# Power_outputs.net
KiCad netlist of a schematic drawn in Altium Designer
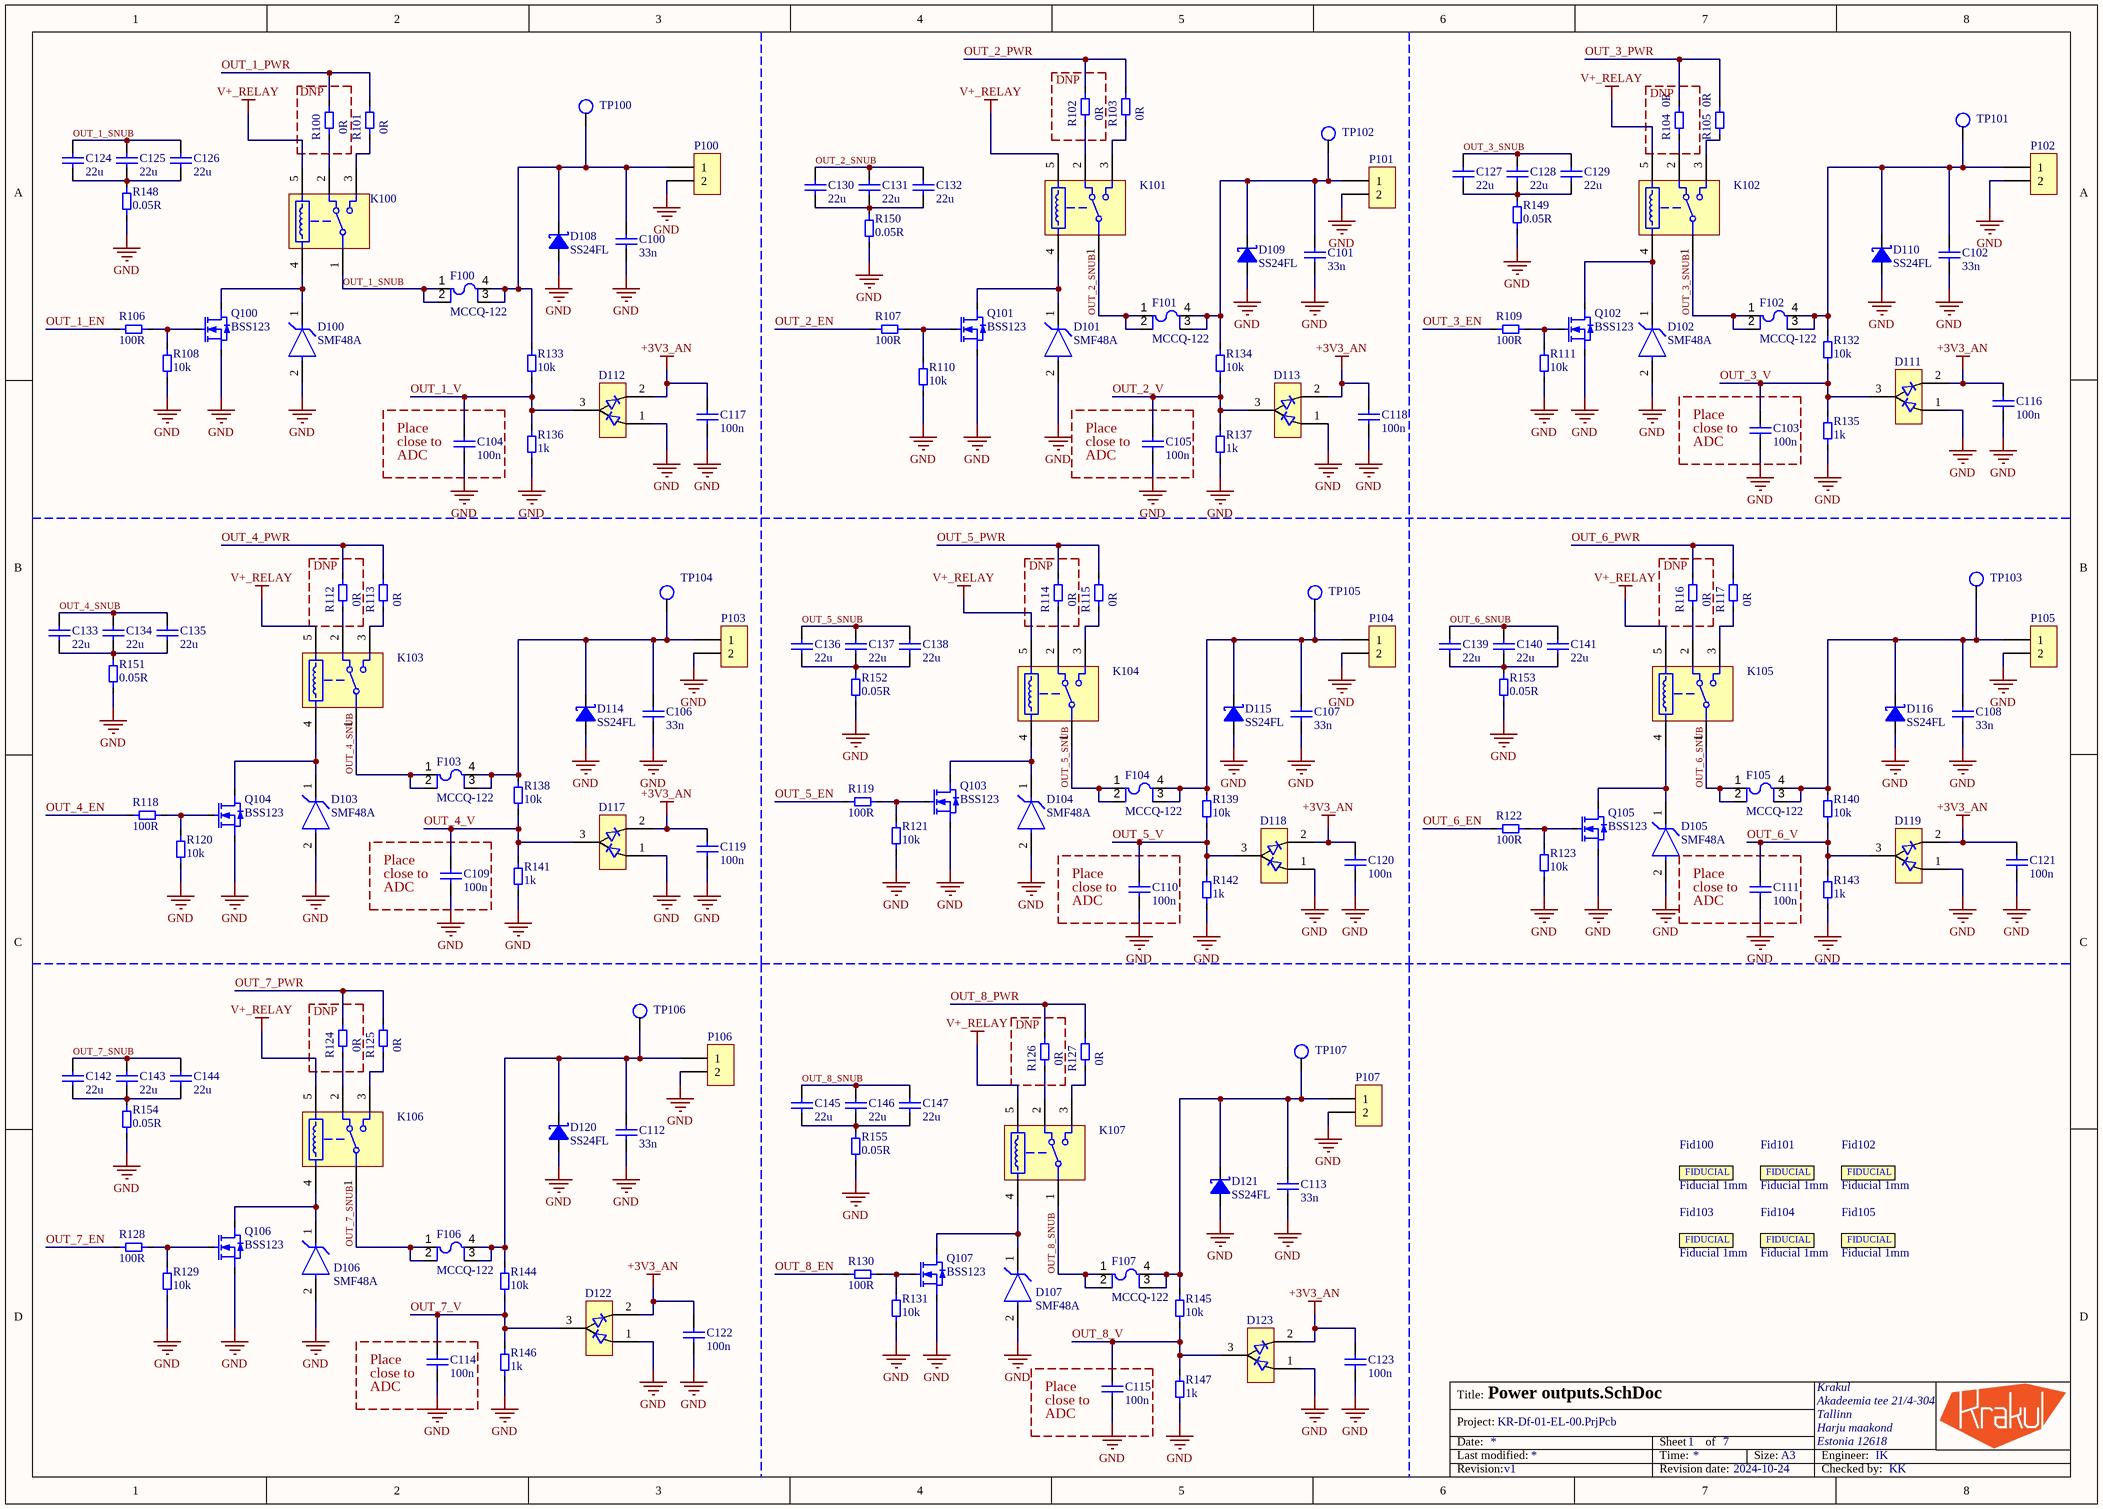
[diagram p0: Power outputs.SchDoc]

(export (version "E")
  (design (tool "Eeschema 10.0.6"))
  (components
    (comp (ref "C100")
      (value "33n")
      (footprint "MLCC_0805_M")
      (description "MLCC, 0805, 33n, 10%, 50V, X7R")
      (fields (field (name "VOLTAGE") "50V") (field (name "TOLERANCE") "10%"))
      (libsource (lib "Krakul Vault") (part "CAPACITOR_NONPOL_IEC"))
    )
    (comp (ref "C101")
      (value "33n")
      (footprint "MLCC_0805_M")
      (description "MLCC, 0805, 33n, 10%, 50V, X7R")
      (fields (field (name "VOLTAGE") "50V") (field (name "TOLERANCE") "10%"))
      (libsource (lib "Krakul Vault") (part "CAPACITOR_NONPOL_IEC"))
    )
    (comp (ref "C102")
      (value "33n")
      (footprint "MLCC_0805_M")
      (description "MLCC, 0805, 33n, 10%, 50V, X7R")
      (fields (field (name "VOLTAGE") "50V") (field (name "TOLERANCE") "10%"))
      (libsource (lib "Krakul Vault") (part "CAPACITOR_NONPOL_IEC"))
    )
    (comp (ref "C103")
      (value "100n")
      (footprint "MLCC_0402_M")
      (description "MLCC, 0402, 100n, 10%, 10V, X5R")
      (fields (field (name "TOLERANCE") "10%") (field (name "MANUFACTURER") "Any"))
      (libsource (lib "Krakul Vault") (part "CAPACITOR_NONPOL_IEC"))
    )
    (comp (ref "C104")
      (value "100n")
      (footprint "MLCC_0402_M")
      (description "MLCC, 0402, 100n, 10%, 10V, X5R")
      (fields (field (name "TOLERANCE") "10%") (field (name "MANUFACTURER") "Any"))
      (libsource (lib "Krakul Vault") (part "CAPACITOR_NONPOL_IEC"))
    )
    (comp (ref "C105")
      (value "100n")
      (footprint "MLCC_0402_M")
      (description "MLCC, 0402, 100n, 10%, 10V, X5R")
      (fields (field (name "TOLERANCE") "10%") (field (name "MANUFACTURER") "Any"))
      (libsource (lib "Krakul Vault") (part "CAPACITOR_NONPOL_IEC"))
    )
    (comp (ref "C106")
      (value "33n")
      (footprint "MLCC_0805_M")
      (description "MLCC, 0805, 33n, 10%, 50V, X7R")
      (fields (field (name "VOLTAGE") "50V") (field (name "TOLERANCE") "10%"))
      (libsource (lib "Krakul Vault") (part "CAPACITOR_NONPOL_IEC"))
    )
    (comp (ref "C107")
      (value "33n")
      (footprint "MLCC_0805_M")
      (description "MLCC, 0805, 33n, 10%, 50V, X7R")
      (fields (field (name "VOLTAGE") "50V") (field (name "TOLERANCE") "10%"))
      (libsource (lib "Krakul Vault") (part "CAPACITOR_NONPOL_IEC"))
    )
    (comp (ref "C108")
      (value "33n")
      (footprint "MLCC_0805_M")
      (description "MLCC, 0805, 33n, 10%, 50V, X7R")
      (fields (field (name "VOLTAGE") "50V") (field (name "TOLERANCE") "10%"))
      (libsource (lib "Krakul Vault") (part "CAPACITOR_NONPOL_IEC"))
    )
    (comp (ref "C109")
      (value "100n")
      (footprint "MLCC_0402_M")
      (description "MLCC, 0402, 100n, 10%, 10V, X5R")
      (fields (field (name "TOLERANCE") "10%") (field (name "MANUFACTURER") "Any"))
      (libsource (lib "Krakul Vault") (part "CAPACITOR_NONPOL_IEC"))
    )
    (comp (ref "C110")
      (value "100n")
      (footprint "MLCC_0402_M")
      (description "MLCC, 0402, 100n, 10%, 10V, X5R")
      (fields (field (name "TOLERANCE") "10%") (field (name "MANUFACTURER") "Any"))
      (libsource (lib "Krakul Vault") (part "CAPACITOR_NONPOL_IEC"))
    )
    (comp (ref "C111")
      (value "100n")
      (footprint "MLCC_0402_M")
      (description "MLCC, 0402, 100n, 10%, 10V, X5R")
      (fields (field (name "TOLERANCE") "10%") (field (name "MANUFACTURER") "Any"))
      (libsource (lib "Krakul Vault") (part "CAPACITOR_NONPOL_IEC"))
    )
    (comp (ref "C112")
      (value "33n")
      (footprint "MLCC_0805_M")
      (description "MLCC, 0805, 33n, 10%, 50V, X7R")
      (fields (field (name "VOLTAGE") "50V") (field (name "TOLERANCE") "10%"))
      (libsource (lib "Krakul Vault") (part "CAPACITOR_NONPOL_IEC"))
    )
    (comp (ref "C113")
      (value "33n")
      (footprint "MLCC_0805_M")
      (description "MLCC, 0805, 33n, 10%, 50V, X7R")
      (fields (field (name "VOLTAGE") "50V") (field (name "TOLERANCE") "10%"))
      (libsource (lib "Krakul Vault") (part "CAPACITOR_NONPOL_IEC"))
    )
    (comp (ref "C114")
      (value "100n")
      (footprint "MLCC_0402_M")
      (description "MLCC, 0402, 100n, 10%, 10V, X5R")
      (fields (field (name "TOLERANCE") "10%") (field (name "MANUFACTURER") "Any"))
      (libsource (lib "Krakul Vault") (part "CAPACITOR_NONPOL_IEC"))
    )
    (comp (ref "C115")
      (value "100n")
      (footprint "MLCC_0402_M")
      (description "MLCC, 0402, 100n, 10%, 10V, X5R")
      (fields (field (name "TOLERANCE") "10%") (field (name "MANUFACTURER") "Any"))
      (libsource (lib "Krakul Vault") (part "CAPACITOR_NONPOL_IEC"))
    )
    (comp (ref "C116")
      (value "100n")
      (footprint "MLCC_0402_M")
      (description "MLCC, 0402, 100n, 10%, 10V, X5R")
      (fields (field (name "TOLERANCE") "10%") (field (name "MANUFACTURER") "Any"))
      (libsource (lib "Krakul Vault") (part "CAPACITOR_NONPOL_IEC"))
    )
    (comp (ref "C117")
      (value "100n")
      (footprint "MLCC_0402_M")
      (description "MLCC, 0402, 100n, 10%, 10V, X5R")
      (fields (field (name "TOLERANCE") "10%") (field (name "MANUFACTURER") "Any"))
      (libsource (lib "Krakul Vault") (part "CAPACITOR_NONPOL_IEC"))
    )
    (comp (ref "C118")
      (value "100n")
      (footprint "MLCC_0402_M")
      (description "MLCC, 0402, 100n, 10%, 10V, X5R")
      (fields (field (name "TOLERANCE") "10%") (field (name "MANUFACTURER") "Any"))
      (libsource (lib "Krakul Vault") (part "CAPACITOR_NONPOL_IEC"))
    )
    (comp (ref "C119")
      (value "100n")
      (footprint "MLCC_0402_M")
      (description "MLCC, 0402, 100n, 10%, 10V, X5R")
      (fields (field (name "TOLERANCE") "10%") (field (name "MANUFACTURER") "Any"))
      (libsource (lib "Krakul Vault") (part "CAPACITOR_NONPOL_IEC"))
    )
    (comp (ref "C120")
      (value "100n")
      (footprint "MLCC_0402_M")
      (description "MLCC, 0402, 100n, 10%, 10V, X5R")
      (fields (field (name "TOLERANCE") "10%") (field (name "MANUFACTURER") "Any"))
      (libsource (lib "Krakul Vault") (part "CAPACITOR_NONPOL_IEC"))
    )
    (comp (ref "C121")
      (value "100n")
      (footprint "MLCC_0402_M")
      (description "MLCC, 0402, 100n, 10%, 10V, X5R")
      (fields (field (name "TOLERANCE") "10%") (field (name "MANUFACTURER") "Any"))
      (libsource (lib "Krakul Vault") (part "CAPACITOR_NONPOL_IEC"))
    )
    (comp (ref "C122")
      (value "100n")
      (footprint "MLCC_0402_M")
      (description "MLCC, 0402, 100n, 10%, 10V, X5R")
      (fields (field (name "TOLERANCE") "10%") (field (name "MANUFACTURER") "Any"))
      (libsource (lib "Krakul Vault") (part "CAPACITOR_NONPOL_IEC"))
    )
    (comp (ref "C123")
      (value "100n")
      (footprint "MLCC_0402_M")
      (description "MLCC, 0402, 100n, 10%, 10V, X5R")
      (fields (field (name "TOLERANCE") "10%") (field (name "MANUFACTURER") "Any"))
      (libsource (lib "Krakul Vault") (part "CAPACITOR_NONPOL_IEC"))
    )
    (comp (ref "C124")
      (value "22u")
      (footprint "MLCC_0805_M")
      (description "MLCC, 0805, 22u, 20%, 35V, X5R")
      (fields (field (name "VOLTAGE") "35V") (field (name "TOLERANCE") "20%"))
      (libsource (lib "Krakul Vault") (part "CAPACITOR_NONPOL_IEC"))
    )
    (comp (ref "C125")
      (value "22u")
      (footprint "MLCC_0805_M")
      (description "MLCC, 0805, 22u, 20%, 35V, X5R")
      (fields (field (name "VOLTAGE") "35V") (field (name "TOLERANCE") "20%"))
      (libsource (lib "Krakul Vault") (part "CAPACITOR_NONPOL_IEC"))
    )
    (comp (ref "C126")
      (value "22u")
      (footprint "MLCC_0805_M")
      (description "MLCC, 0805, 22u, 20%, 35V, X5R")
      (fields (field (name "VOLTAGE") "35V") (field (name "TOLERANCE") "20%"))
      (libsource (lib "Krakul Vault") (part "CAPACITOR_NONPOL_IEC"))
    )
    (comp (ref "C127")
      (value "22u")
      (footprint "MLCC_0805_M")
      (description "MLCC, 0805, 22u, 20%, 35V, X5R")
      (fields (field (name "VOLTAGE") "35V") (field (name "TOLERANCE") "20%"))
      (libsource (lib "Krakul Vault") (part "CAPACITOR_NONPOL_IEC"))
    )
    (comp (ref "C128")
      (value "22u")
      (footprint "MLCC_0805_M")
      (description "MLCC, 0805, 22u, 20%, 35V, X5R")
      (fields (field (name "VOLTAGE") "35V") (field (name "TOLERANCE") "20%"))
      (libsource (lib "Krakul Vault") (part "CAPACITOR_NONPOL_IEC"))
    )
    (comp (ref "C129")
      (value "22u")
      (footprint "MLCC_0805_M")
      (description "MLCC, 0805, 22u, 20%, 35V, X5R")
      (fields (field (name "VOLTAGE") "35V") (field (name "TOLERANCE") "20%"))
      (libsource (lib "Krakul Vault") (part "CAPACITOR_NONPOL_IEC"))
    )
    (comp (ref "C130")
      (value "22u")
      (footprint "MLCC_0805_M")
      (description "MLCC, 0805, 22u, 20%, 35V, X5R")
      (fields (field (name "VOLTAGE") "35V") (field (name "TOLERANCE") "20%"))
      (libsource (lib "Krakul Vault") (part "CAPACITOR_NONPOL_IEC"))
    )
    (comp (ref "C131")
      (value "22u")
      (footprint "MLCC_0805_M")
      (description "MLCC, 0805, 22u, 20%, 35V, X5R")
      (fields (field (name "VOLTAGE") "35V") (field (name "TOLERANCE") "20%"))
      (libsource (lib "Krakul Vault") (part "CAPACITOR_NONPOL_IEC"))
    )
    (comp (ref "C132")
      (value "22u")
      (footprint "MLCC_0805_M")
      (description "MLCC, 0805, 22u, 20%, 35V, X5R")
      (fields (field (name "VOLTAGE") "35V") (field (name "TOLERANCE") "20%"))
      (libsource (lib "Krakul Vault") (part "CAPACITOR_NONPOL_IEC"))
    )
    (comp (ref "C133")
      (value "22u")
      (footprint "MLCC_0805_M")
      (description "MLCC, 0805, 22u, 20%, 35V, X5R")
      (fields (field (name "VOLTAGE") "35V") (field (name "TOLERANCE") "20%"))
      (libsource (lib "Krakul Vault") (part "CAPACITOR_NONPOL_IEC"))
    )
    (comp (ref "C134")
      (value "22u")
      (footprint "MLCC_0805_M")
      (description "MLCC, 0805, 22u, 20%, 35V, X5R")
      (fields (field (name "VOLTAGE") "35V") (field (name "TOLERANCE") "20%"))
      (libsource (lib "Krakul Vault") (part "CAPACITOR_NONPOL_IEC"))
    )
    (comp (ref "C135")
      (value "22u")
      (footprint "MLCC_0805_M")
      (description "MLCC, 0805, 22u, 20%, 35V, X5R")
      (fields (field (name "VOLTAGE") "35V") (field (name "TOLERANCE") "20%"))
      (libsource (lib "Krakul Vault") (part "CAPACITOR_NONPOL_IEC"))
    )
    (comp (ref "C136")
      (value "22u")
      (footprint "MLCC_0805_M")
      (description "MLCC, 0805, 22u, 20%, 35V, X5R")
      (fields (field (name "VOLTAGE") "35V") (field (name "TOLERANCE") "20%"))
      (libsource (lib "Krakul Vault") (part "CAPACITOR_NONPOL_IEC"))
    )
    (comp (ref "C137")
      (value "22u")
      (footprint "MLCC_0805_M")
      (description "MLCC, 0805, 22u, 20%, 35V, X5R")
      (fields (field (name "VOLTAGE") "35V") (field (name "TOLERANCE") "20%"))
      (libsource (lib "Krakul Vault") (part "CAPACITOR_NONPOL_IEC"))
    )
    (comp (ref "C138")
      (value "22u")
      (footprint "MLCC_0805_M")
      (description "MLCC, 0805, 22u, 20%, 35V, X5R")
      (fields (field (name "VOLTAGE") "35V") (field (name "TOLERANCE") "20%"))
      (libsource (lib "Krakul Vault") (part "CAPACITOR_NONPOL_IEC"))
    )
    (comp (ref "C139")
      (value "22u")
      (footprint "MLCC_0805_M")
      (description "MLCC, 0805, 22u, 20%, 35V, X5R")
      (fields (field (name "VOLTAGE") "35V") (field (name "TOLERANCE") "20%"))
      (libsource (lib "Krakul Vault") (part "CAPACITOR_NONPOL_IEC"))
    )
    (comp (ref "C140")
      (value "22u")
      (footprint "MLCC_0805_M")
      (description "MLCC, 0805, 22u, 20%, 35V, X5R")
      (fields (field (name "VOLTAGE") "35V") (field (name "TOLERANCE") "20%"))
      (libsource (lib "Krakul Vault") (part "CAPACITOR_NONPOL_IEC"))
    )
    (comp (ref "C141")
      (value "22u")
      (footprint "MLCC_0805_M")
      (description "MLCC, 0805, 22u, 20%, 35V, X5R")
      (fields (field (name "VOLTAGE") "35V") (field (name "TOLERANCE") "20%"))
      (libsource (lib "Krakul Vault") (part "CAPACITOR_NONPOL_IEC"))
    )
    (comp (ref "C142")
      (value "22u")
      (footprint "MLCC_0805_M")
      (description "MLCC, 0805, 22u, 20%, 35V, X5R")
      (fields (field (name "VOLTAGE") "35V") (field (name "TOLERANCE") "20%"))
      (libsource (lib "Krakul Vault") (part "CAPACITOR_NONPOL_IEC"))
    )
    (comp (ref "C143")
      (value "22u")
      (footprint "MLCC_0805_M")
      (description "MLCC, 0805, 22u, 20%, 35V, X5R")
      (fields (field (name "VOLTAGE") "35V") (field (name "TOLERANCE") "20%"))
      (libsource (lib "Krakul Vault") (part "CAPACITOR_NONPOL_IEC"))
    )
    (comp (ref "C144")
      (value "22u")
      (footprint "MLCC_0805_M")
      (description "MLCC, 0805, 22u, 20%, 35V, X5R")
      (fields (field (name "VOLTAGE") "35V") (field (name "TOLERANCE") "20%"))
      (libsource (lib "Krakul Vault") (part "CAPACITOR_NONPOL_IEC"))
    )
    (comp (ref "C145")
      (value "22u")
      (footprint "MLCC_0805_M")
      (description "MLCC, 0805, 22u, 20%, 35V, X5R")
      (fields (field (name "VOLTAGE") "35V") (field (name "TOLERANCE") "20%"))
      (libsource (lib "Krakul Vault") (part "CAPACITOR_NONPOL_IEC"))
    )
    (comp (ref "C146")
      (value "22u")
      (footprint "MLCC_0805_M")
      (description "MLCC, 0805, 22u, 20%, 35V, X5R")
      (fields (field (name "VOLTAGE") "35V") (field (name "TOLERANCE") "20%"))
      (libsource (lib "Krakul Vault") (part "CAPACITOR_NONPOL_IEC"))
    )
    (comp (ref "C147")
      (value "22u")
      (footprint "MLCC_0805_M")
      (description "MLCC, 0805, 22u, 20%, 35V, X5R")
      (fields (field (name "VOLTAGE") "35V") (field (name "TOLERANCE") "20%"))
      (libsource (lib "Krakul Vault") (part "CAPACITOR_NONPOL_IEC"))
    )
    (comp (ref "D100")
      (value "SMF48A")
      (footprint "FP-SMF48A-MFG")
      (description "Diode TVS Single Uni-Dir 48V 200W 2-Pin SOD-123F T/R")
      (fields (field (name "MANUFACTURER") "Littelfuse"))
      (libsource (lib "Krakul Vault") (part "f813f71cba58e380607f5dd3caf9714"))
    )
    (comp (ref "D101")
      (value "SMF48A")
      (footprint "FP-SMF48A-MFG")
      (description "Diode TVS Single Uni-Dir 48V 200W 2-Pin SOD-123F T/R")
      (fields (field (name "MANUFACTURER") "Littelfuse"))
      (libsource (lib "Krakul Vault") (part "f813f71cba58e380607f5dd3caf9714"))
    )
    (comp (ref "D102")
      (value "SMF48A")
      (footprint "FP-SMF48A-MFG")
      (description "Diode TVS Single Uni-Dir 48V 200W 2-Pin SOD-123F T/R")
      (fields (field (name "MANUFACTURER") "Littelfuse"))
      (libsource (lib "Krakul Vault") (part "f813f71cba58e380607f5dd3caf9714"))
    )
    (comp (ref "D103")
      (value "SMF48A")
      (footprint "FP-SMF48A-MFG")
      (description "Diode TVS Single Uni-Dir 48V 200W 2-Pin SOD-123F T/R")
      (fields (field (name "MANUFACTURER") "Littelfuse"))
      (libsource (lib "Krakul Vault") (part "f813f71cba58e380607f5dd3caf9714"))
    )
    (comp (ref "D104")
      (value "SMF48A")
      (footprint "FP-SMF48A-MFG")
      (description "Diode TVS Single Uni-Dir 48V 200W 2-Pin SOD-123F T/R")
      (fields (field (name "MANUFACTURER") "Littelfuse"))
      (libsource (lib "Krakul Vault") (part "f813f71cba58e380607f5dd3caf9714"))
    )
    (comp (ref "D105")
      (value "SMF48A")
      (footprint "FP-SMF48A-MFG")
      (description "Diode TVS Single Uni-Dir 48V 200W 2-Pin SOD-123F T/R")
      (fields (field (name "MANUFACTURER") "Littelfuse"))
      (libsource (lib "Krakul Vault") (part "f813f71cba58e380607f5dd3caf9714"))
    )
    (comp (ref "D106")
      (value "SMF48A")
      (footprint "FP-SMF48A-MFG")
      (description "Diode TVS Single Uni-Dir 48V 200W 2-Pin SOD-123F T/R")
      (fields (field (name "MANUFACTURER") "Littelfuse"))
      (libsource (lib "Krakul Vault") (part "f813f71cba58e380607f5dd3caf9714"))
    )
    (comp (ref "D107")
      (value "SMF48A")
      (footprint "FP-SMF48A-MFG")
      (description "Diode TVS Single Uni-Dir 48V 200W 2-Pin SOD-123F T/R")
      (fields (field (name "MANUFACTURER") "Littelfuse"))
      (libsource (lib "Krakul Vault") (part "f813f71cba58e380607f5dd3caf9714"))
    )
    (comp (ref "D108")
      (value "SS24FL")
      (footprint "SOD-123F")
      (description "Diode Schottky 40V 2A Surface Mount SOD-123F")
      (fields (field (name "MANUFACTURER") "ON Semiconductor"))
      (libsource (lib "Krakul Vault") (part "Schottky generic 2 pins"))
    )
    (comp (ref "D109")
      (value "SS24FL")
      (footprint "SOD-123F")
      (description "Diode Schottky 40V 2A Surface Mount SOD-123F")
      (fields (field (name "MANUFACTURER") "ON Semiconductor"))
      (libsource (lib "Krakul Vault") (part "Schottky generic 2 pins"))
    )
    (comp (ref "D110")
      (value "SS24FL")
      (footprint "SOD-123F")
      (description "Diode Schottky 40V 2A Surface Mount SOD-123F")
      (fields (field (name "MANUFACTURER") "ON Semiconductor"))
      (libsource (lib "Krakul Vault") (part "Schottky generic 2 pins"))
    )
    (comp (ref "D111")
      (value "BAT6404WH6327XTSA1")
      (footprint "SOT323, SC70")
      (description "Diode Array 1 Pair Series Connection Schottky 40V 120mA Surface Mount SC-70, SOT-323")
      (fields (field (name "MANUFACTURER") "Infineon"))
      (libsource (lib "Krakul Vault") (part "BAT64-04W"))
    )
    (comp (ref "D112")
      (value "BAT6404WH6327XTSA1")
      (footprint "SOT323, SC70")
      (description "Diode Array 1 Pair Series Connection Schottky 40V 120mA Surface Mount SC-70, SOT-323")
      (fields (field (name "MANUFACTURER") "Infineon"))
      (libsource (lib "Krakul Vault") (part "BAT64-04W"))
    )
    (comp (ref "D113")
      (value "BAT6404WH6327XTSA1")
      (footprint "SOT323, SC70")
      (description "Diode Array 1 Pair Series Connection Schottky 40V 120mA Surface Mount SC-70, SOT-323")
      (fields (field (name "MANUFACTURER") "Infineon"))
      (libsource (lib "Krakul Vault") (part "BAT64-04W"))
    )
    (comp (ref "D114")
      (value "SS24FL")
      (footprint "SOD-123F")
      (description "Diode Schottky 40V 2A Surface Mount SOD-123F")
      (fields (field (name "MANUFACTURER") "ON Semiconductor"))
      (libsource (lib "Krakul Vault") (part "Schottky generic 2 pins"))
    )
    (comp (ref "D115")
      (value "SS24FL")
      (footprint "SOD-123F")
      (description "Diode Schottky 40V 2A Surface Mount SOD-123F")
      (fields (field (name "MANUFACTURER") "ON Semiconductor"))
      (libsource (lib "Krakul Vault") (part "Schottky generic 2 pins"))
    )
    (comp (ref "D116")
      (value "SS24FL")
      (footprint "SOD-123F")
      (description "Diode Schottky 40V 2A Surface Mount SOD-123F")
      (fields (field (name "MANUFACTURER") "ON Semiconductor"))
      (libsource (lib "Krakul Vault") (part "Schottky generic 2 pins"))
    )
    (comp (ref "D117")
      (value "BAT6404WH6327XTSA1")
      (footprint "SOT323, SC70")
      (description "Diode Array 1 Pair Series Connection Schottky 40V 120mA Surface Mount SC-70, SOT-323")
      (fields (field (name "MANUFACTURER") "Infineon"))
      (libsource (lib "Krakul Vault") (part "BAT64-04W"))
    )
    (comp (ref "D118")
      (value "BAT6404WH6327XTSA1")
      (footprint "SOT323, SC70")
      (description "Diode Array 1 Pair Series Connection Schottky 40V 120mA Surface Mount SC-70, SOT-323")
      (fields (field (name "MANUFACTURER") "Infineon"))
      (libsource (lib "Krakul Vault") (part "BAT64-04W"))
    )
    (comp (ref "D119")
      (value "BAT6404WH6327XTSA1")
      (footprint "SOT323, SC70")
      (description "Diode Array 1 Pair Series Connection Schottky 40V 120mA Surface Mount SC-70, SOT-323")
      (fields (field (name "MANUFACTURER") "Infineon"))
      (libsource (lib "Krakul Vault") (part "BAT64-04W"))
    )
    (comp (ref "D120")
      (value "SS24FL")
      (footprint "SOD-123F")
      (description "Diode Schottky 40V 2A Surface Mount SOD-123F")
      (fields (field (name "MANUFACTURER") "ON Semiconductor"))
      (libsource (lib "Krakul Vault") (part "Schottky generic 2 pins"))
    )
    (comp (ref "D121")
      (value "SS24FL")
      (footprint "SOD-123F")
      (description "Diode Schottky 40V 2A Surface Mount SOD-123F")
      (fields (field (name "MANUFACTURER") "ON Semiconductor"))
      (libsource (lib "Krakul Vault") (part "Schottky generic 2 pins"))
    )
    (comp (ref "D122")
      (value "BAT6404WH6327XTSA1")
      (footprint "SOT323, SC70")
      (description "Diode Array 1 Pair Series Connection Schottky 40V 120mA Surface Mount SC-70, SOT-323")
      (fields (field (name "MANUFACTURER") "Infineon"))
      (libsource (lib "Krakul Vault") (part "BAT64-04W"))
    )
    (comp (ref "D123")
      (value "BAT6404WH6327XTSA1")
      (footprint "SOT323, SC70")
      (description "Diode Array 1 Pair Series Connection Schottky 40V 120mA Surface Mount SC-70, SOT-323")
      (fields (field (name "MANUFACTURER") "Infineon"))
      (libsource (lib "Krakul Vault") (part "BAT64-04W"))
    )
    (comp (ref "F100")
      (value "MCCQ-122")
      (footprint "MCCQ-122-Footprint-1")
      (description "Fuseholder, Pcb Mount, Mini Blade")
      (fields (field (name "MANUFACTURER") "Multicomp"))
      (libsource (lib "Krakul Vault") (part "MCCQ-122-Symbol-1"))
    )
    (comp (ref "F101")
      (value "MCCQ-122")
      (footprint "MCCQ-122-Footprint-1")
      (description "Fuseholder, Pcb Mount, Mini Blade")
      (fields (field (name "MANUFACTURER") "Multicomp"))
      (libsource (lib "Krakul Vault") (part "MCCQ-122-Symbol-1"))
    )
    (comp (ref "F102")
      (value "MCCQ-122")
      (footprint "MCCQ-122-Footprint-1")
      (description "Fuseholder, Pcb Mount, Mini Blade")
      (fields (field (name "MANUFACTURER") "Multicomp"))
      (libsource (lib "Krakul Vault") (part "MCCQ-122-Symbol-1"))
    )
    (comp (ref "F103")
      (value "MCCQ-122")
      (footprint "MCCQ-122-Footprint-1")
      (description "Fuseholder, Pcb Mount, Mini Blade")
      (fields (field (name "MANUFACTURER") "Multicomp"))
      (libsource (lib "Krakul Vault") (part "MCCQ-122-Symbol-1"))
    )
    (comp (ref "F104")
      (value "MCCQ-122")
      (footprint "MCCQ-122-Footprint-1")
      (description "Fuseholder, Pcb Mount, Mini Blade")
      (fields (field (name "MANUFACTURER") "Multicomp"))
      (libsource (lib "Krakul Vault") (part "MCCQ-122-Symbol-1"))
    )
    (comp (ref "F105")
      (value "MCCQ-122")
      (footprint "MCCQ-122-Footprint-1")
      (description "Fuseholder, Pcb Mount, Mini Blade")
      (fields (field (name "MANUFACTURER") "Multicomp"))
      (libsource (lib "Krakul Vault") (part "MCCQ-122-Symbol-1"))
    )
    (comp (ref "F106")
      (value "MCCQ-122")
      (footprint "MCCQ-122-Footprint-1")
      (description "Fuseholder, Pcb Mount, Mini Blade")
      (fields (field (name "MANUFACTURER") "Multicomp"))
      (libsource (lib "Krakul Vault") (part "MCCQ-122-Symbol-1"))
    )
    (comp (ref "F107")
      (value "MCCQ-122")
      (footprint "MCCQ-122-Footprint-1")
      (description "Fuseholder, Pcb Mount, Mini Blade")
      (fields (field (name "MANUFACTURER") "Multicomp"))
      (libsource (lib "Krakul Vault") (part "MCCQ-122-Symbol-1"))
    )
    (comp (ref "Fid100")
      (value "Fiducial 1mm")
      (footprint "FIDUCIAL 1mm")
      (description "Fiducial, round, 1mm diam")
      (libsource (lib "Krakul Vault") (part "Fiducial"))
    )
    (comp (ref "Fid101")
      (value "Fiducial 1mm")
      (footprint "FIDUCIAL 1mm")
      (description "Fiducial, round, 1mm diam")
      (libsource (lib "Krakul Vault") (part "Fiducial"))
    )
    (comp (ref "Fid102")
      (value "Fiducial 1mm")
      (footprint "FIDUCIAL 1mm")
      (description "Fiducial, round, 1mm diam")
      (libsource (lib "Krakul Vault") (part "Fiducial"))
    )
    (comp (ref "Fid103")
      (value "Fiducial 1mm")
      (footprint "FIDUCIAL 1mm")
      (description "Fiducial, round, 1mm diam")
      (libsource (lib "Krakul Vault") (part "Fiducial"))
    )
    (comp (ref "Fid104")
      (value "Fiducial 1mm")
      (footprint "FIDUCIAL 1mm")
      (description "Fiducial, round, 1mm diam")
      (libsource (lib "Krakul Vault") (part "Fiducial"))
    )
    (comp (ref "Fid105")
      (value "Fiducial 1mm")
      (footprint "FIDUCIAL 1mm")
      (description "Fiducial, round, 1mm diam")
      (libsource (lib "Krakul Vault") (part "Fiducial"))
    )
    (comp (ref "K100")
      (value "J107F1CS205VDC.45")
      (footprint "J107F1CS205VDC.45")
      (description "RELAY GEN PURPOSE SPDT 20A 5V")
      (fields (field (name "MANUFACTURER") "CIT Relay and Switch"))
      (libsource (lib "Krakul Vault") (part "J107F1CS205VDC.45"))
    )
    (comp (ref "K101")
      (value "J107F1CS205VDC.45")
      (footprint "J107F1CS205VDC.45")
      (description "RELAY GEN PURPOSE SPDT 20A 5V")
      (fields (field (name "MANUFACTURER") "CIT Relay and Switch"))
      (libsource (lib "Krakul Vault") (part "J107F1CS205VDC.45"))
    )
    (comp (ref "K102")
      (value "J107F1CS205VDC.45")
      (footprint "J107F1CS205VDC.45")
      (description "RELAY GEN PURPOSE SPDT 20A 5V")
      (fields (field (name "MANUFACTURER") "CIT Relay and Switch"))
      (libsource (lib "Krakul Vault") (part "J107F1CS205VDC.45"))
    )
    (comp (ref "K103")
      (value "J107F1CS205VDC.45")
      (footprint "J107F1CS205VDC.45")
      (description "RELAY GEN PURPOSE SPDT 20A 5V")
      (fields (field (name "MANUFACTURER") "CIT Relay and Switch"))
      (libsource (lib "Krakul Vault") (part "J107F1CS205VDC.45"))
    )
    (comp (ref "K104")
      (value "J107F1CS205VDC.45")
      (footprint "J107F1CS205VDC.45")
      (description "RELAY GEN PURPOSE SPDT 20A 5V")
      (fields (field (name "MANUFACTURER") "CIT Relay and Switch"))
      (libsource (lib "Krakul Vault") (part "J107F1CS205VDC.45"))
    )
    (comp (ref "K105")
      (value "J107F1CS205VDC.45")
      (footprint "J107F1CS205VDC.45")
      (description "RELAY GEN PURPOSE SPDT 20A 5V")
      (fields (field (name "MANUFACTURER") "CIT Relay and Switch"))
      (libsource (lib "Krakul Vault") (part "J107F1CS205VDC.45"))
    )
    (comp (ref "K106")
      (value "J107F1CS205VDC.45")
      (footprint "J107F1CS205VDC.45")
      (description "RELAY GEN PURPOSE SPDT 20A 5V")
      (fields (field (name "MANUFACTURER") "CIT Relay and Switch"))
      (libsource (lib "Krakul Vault") (part "J107F1CS205VDC.45"))
    )
    (comp (ref "K107")
      (value "J107F1CS205VDC.45")
      (footprint "J107F1CS205VDC.45")
      (description "RELAY GEN PURPOSE SPDT 20A 5V")
      (fields (field (name "MANUFACTURER") "CIT Relay and Switch"))
      (libsource (lib "Krakul Vault") (part "J107F1CS205VDC.45"))
    )
    (comp (ref "P100")
      (value "DGPS2.5R-5.0-02P")
      (footprint "DGPS2.5R-5.0-02P-Footprint-1")
      (description "Spring loaded terminal block")
      (fields (field (name "MANUFACTURER") "Degson"))
      (libsource (lib "Krakul Vault") (part "2POS GENERIC"))
    )
    (comp (ref "P101")
      (value "DGPS2.5R-5.0-02P")
      (footprint "DGPS2.5R-5.0-02P-Footprint-1")
      (description "Spring loaded terminal block")
      (fields (field (name "MANUFACTURER") "Degson"))
      (libsource (lib "Krakul Vault") (part "2POS GENERIC"))
    )
    (comp (ref "P102")
      (value "DGPS2.5R-5.0-02P")
      (footprint "DGPS2.5R-5.0-02P-Footprint-1")
      (description "Spring loaded terminal block")
      (fields (field (name "MANUFACTURER") "Degson"))
      (libsource (lib "Krakul Vault") (part "2POS GENERIC"))
    )
    (comp (ref "P103")
      (value "DGPS2.5R-5.0-02P")
      (footprint "DGPS2.5R-5.0-02P-Footprint-1")
      (description "Spring loaded terminal block")
      (fields (field (name "MANUFACTURER") "Degson"))
      (libsource (lib "Krakul Vault") (part "2POS GENERIC"))
    )
    (comp (ref "P104")
      (value "DGPS2.5R-5.0-02P")
      (footprint "DGPS2.5R-5.0-02P-Footprint-1")
      (description "Spring loaded terminal block")
      (fields (field (name "MANUFACTURER") "Degson"))
      (libsource (lib "Krakul Vault") (part "2POS GENERIC"))
    )
    (comp (ref "P105")
      (value "DGPS2.5R-5.0-02P")
      (footprint "DGPS2.5R-5.0-02P-Footprint-1")
      (description "Spring loaded terminal block")
      (fields (field (name "MANUFACTURER") "Degson"))
      (libsource (lib "Krakul Vault") (part "2POS GENERIC"))
    )
    (comp (ref "P106")
      (value "DGPS2.5R-5.0-02P")
      (footprint "DGPS2.5R-5.0-02P-Footprint-1")
      (description "Spring loaded terminal block")
      (fields (field (name "MANUFACTURER") "Degson"))
      (libsource (lib "Krakul Vault") (part "2POS GENERIC"))
    )
    (comp (ref "P107")
      (value "DGPS2.5R-5.0-02P")
      (footprint "DGPS2.5R-5.0-02P-Footprint-1")
      (description "Spring loaded terminal block")
      (fields (field (name "MANUFACTURER") "Degson"))
      (libsource (lib "Krakul Vault") (part "2POS GENERIC"))
    )
    (comp (ref "Q100")
      (value "BSS123")
      (footprint "SOT-23-3")
      (description "MOSFET N-CH 100V 170MA SOT-23")
      (fields (field (name "MANUFACTURER") "ON Semiconductor") (field (name "VOLTAGE") "100V"))
      (libsource (lib "Krakul Vault") (part "N-CH MOSFET 3-pin SOT"))
    )
    (comp (ref "Q101")
      (value "BSS123")
      (footprint "SOT-23-3")
      (description "MOSFET N-CH 100V 170MA SOT-23")
      (fields (field (name "MANUFACTURER") "ON Semiconductor") (field (name "VOLTAGE") "100V"))
      (libsource (lib "Krakul Vault") (part "N-CH MOSFET 3-pin SOT"))
    )
    (comp (ref "Q102")
      (value "BSS123")
      (footprint "SOT-23-3")
      (description "MOSFET N-CH 100V 170MA SOT-23")
      (fields (field (name "MANUFACTURER") "ON Semiconductor") (field (name "VOLTAGE") "100V"))
      (libsource (lib "Krakul Vault") (part "N-CH MOSFET 3-pin SOT"))
    )
    (comp (ref "Q103")
      (value "BSS123")
      (footprint "SOT-23-3")
      (description "MOSFET N-CH 100V 170MA SOT-23")
      (fields (field (name "MANUFACTURER") "ON Semiconductor") (field (name "VOLTAGE") "100V"))
      (libsource (lib "Krakul Vault") (part "N-CH MOSFET 3-pin SOT"))
    )
    (comp (ref "Q104")
      (value "BSS123")
      (footprint "SOT-23-3")
      (description "MOSFET N-CH 100V 170MA SOT-23")
      (fields (field (name "MANUFACTURER") "ON Semiconductor") (field (name "VOLTAGE") "100V"))
      (libsource (lib "Krakul Vault") (part "N-CH MOSFET 3-pin SOT"))
    )
    (comp (ref "Q105")
      (value "BSS123")
      (footprint "SOT-23-3")
      (description "MOSFET N-CH 100V 170MA SOT-23")
      (fields (field (name "MANUFACTURER") "ON Semiconductor") (field (name "VOLTAGE") "100V"))
      (libsource (lib "Krakul Vault") (part "N-CH MOSFET 3-pin SOT"))
    )
    (comp (ref "Q106")
      (value "BSS123")
      (footprint "SOT-23-3")
      (description "MOSFET N-CH 100V 170MA SOT-23")
      (fields (field (name "MANUFACTURER") "ON Semiconductor") (field (name "VOLTAGE") "100V"))
      (libsource (lib "Krakul Vault") (part "N-CH MOSFET 3-pin SOT"))
    )
    (comp (ref "Q107")
      (value "BSS123")
      (footprint "SOT-23-3")
      (description "MOSFET N-CH 100V 170MA SOT-23")
      (fields (field (name "MANUFACTURER") "ON Semiconductor") (field (name "VOLTAGE") "100V"))
      (libsource (lib "Krakul Vault") (part "N-CH MOSFET 3-pin SOT"))
    )
    (comp (ref "R100")
      (value "TLRZ2BTTD")
      (footprint "TLRZ2BTTD-Footprint-1")
      (description "Res Metal Plate 1206 0 Ohm Sulfur Resistant Pad SMD Automotive T/R")
      (fields (field (name "MANUFACTURER") "KOA Speer Electronics") (field (name "VALUE 2") "0R"))
      (libsource (lib "Krakul Vault") (part "RESISTOR_GENERIC_IEC"))
    )
    (comp (ref "R101")
      (value "TLRZ2BTTD")
      (footprint "TLRZ2BTTD-Footprint-1")
      (description "Res Metal Plate 1206 0 Ohm Sulfur Resistant Pad SMD Automotive T/R")
      (fields (field (name "MANUFACTURER") "KOA Speer Electronics") (field (name "VALUE 2") "0R"))
      (libsource (lib "Krakul Vault") (part "RESISTOR_GENERIC_IEC"))
    )
    (comp (ref "R102")
      (value "TLRZ2BTTD")
      (footprint "TLRZ2BTTD-Footprint-1")
      (description "Res Metal Plate 1206 0 Ohm Sulfur Resistant Pad SMD Automotive T/R")
      (fields (field (name "MANUFACTURER") "KOA Speer Electronics") (field (name "VALUE 2") "0R"))
      (libsource (lib "Krakul Vault") (part "RESISTOR_GENERIC_IEC"))
    )
    (comp (ref "R103")
      (value "TLRZ2BTTD")
      (footprint "TLRZ2BTTD-Footprint-1")
      (description "Res Metal Plate 1206 0 Ohm Sulfur Resistant Pad SMD Automotive T/R")
      (fields (field (name "MANUFACTURER") "KOA Speer Electronics") (field (name "VALUE 2") "0R"))
      (libsource (lib "Krakul Vault") (part "RESISTOR_GENERIC_IEC"))
    )
    (comp (ref "R104")
      (value "TLRZ2BTTD")
      (footprint "TLRZ2BTTD-Footprint-1")
      (description "Res Metal Plate 1206 0 Ohm Sulfur Resistant Pad SMD Automotive T/R")
      (fields (field (name "MANUFACTURER") "KOA Speer Electronics") (field (name "VALUE 2") "0R"))
      (libsource (lib "Krakul Vault") (part "RESISTOR_GENERIC_IEC"))
    )
    (comp (ref "R105")
      (value "TLRZ2BTTD")
      (footprint "TLRZ2BTTD-Footprint-1")
      (description "Res Metal Plate 1206 0 Ohm Sulfur Resistant Pad SMD Automotive T/R")
      (fields (field (name "MANUFACTURER") "KOA Speer Electronics") (field (name "VALUE 2") "0R"))
      (libsource (lib "Krakul Vault") (part "RESISTOR_GENERIC_IEC"))
    )
    (comp (ref "R106")
      (value "100R")
      (footprint "Resistor_0603_M")
      (description "Resistor, 0603, 100R, 1%, 1/10W")
      (fields (field (name "TOLERANCE") "1%") (field (name "POWER") "100mW"))
      (libsource (lib "Krakul Vault") (part "RESISTOR_GENERIC_IEC"))
    )
    (comp (ref "R107")
      (value "100R")
      (footprint "Resistor_0603_M")
      (description "Resistor, 0603, 100R, 1%, 1/10W")
      (fields (field (name "TOLERANCE") "1%") (field (name "POWER") "100mW"))
      (libsource (lib "Krakul Vault") (part "RESISTOR_GENERIC_IEC"))
    )
    (comp (ref "R108")
      (value "10k")
      (footprint "Resistor_0603_M")
      (description "Resistor, 0603, 10k, 1%, 1/10W")
      (fields (field (name "MANUFACTURER") "Any") (field (name "TOLERANCE") "1%"))
      (libsource (lib "Krakul Vault") (part "RESISTOR_GENERIC_IEC"))
    )
    (comp (ref "R109")
      (value "100R")
      (footprint "Resistor_0603_M")
      (description "Resistor, 0603, 100R, 1%, 1/10W")
      (fields (field (name "TOLERANCE") "1%") (field (name "POWER") "100mW"))
      (libsource (lib "Krakul Vault") (part "RESISTOR_GENERIC_IEC"))
    )
    (comp (ref "R110")
      (value "10k")
      (footprint "Resistor_0603_M")
      (description "Resistor, 0603, 10k, 1%, 1/10W")
      (fields (field (name "MANUFACTURER") "Any") (field (name "TOLERANCE") "1%"))
      (libsource (lib "Krakul Vault") (part "RESISTOR_GENERIC_IEC"))
    )
    (comp (ref "R111")
      (value "10k")
      (footprint "Resistor_0603_M")
      (description "Resistor, 0603, 10k, 1%, 1/10W")
      (fields (field (name "MANUFACTURER") "Any") (field (name "TOLERANCE") "1%"))
      (libsource (lib "Krakul Vault") (part "RESISTOR_GENERIC_IEC"))
    )
    (comp (ref "R112")
      (value "TLRZ2BTTD")
      (footprint "TLRZ2BTTD-Footprint-1")
      (description "Res Metal Plate 1206 0 Ohm Sulfur Resistant Pad SMD Automotive T/R")
      (fields (field (name "MANUFACTURER") "KOA Speer Electronics") (field (name "VALUE 2") "0R"))
      (libsource (lib "Krakul Vault") (part "RESISTOR_GENERIC_IEC"))
    )
    (comp (ref "R113")
      (value "TLRZ2BTTD")
      (footprint "TLRZ2BTTD-Footprint-1")
      (description "Res Metal Plate 1206 0 Ohm Sulfur Resistant Pad SMD Automotive T/R")
      (fields (field (name "MANUFACTURER") "KOA Speer Electronics") (field (name "VALUE 2") "0R"))
      (libsource (lib "Krakul Vault") (part "RESISTOR_GENERIC_IEC"))
    )
    (comp (ref "R114")
      (value "TLRZ2BTTD")
      (footprint "TLRZ2BTTD-Footprint-1")
      (description "Res Metal Plate 1206 0 Ohm Sulfur Resistant Pad SMD Automotive T/R")
      (fields (field (name "MANUFACTURER") "KOA Speer Electronics") (field (name "VALUE 2") "0R"))
      (libsource (lib "Krakul Vault") (part "RESISTOR_GENERIC_IEC"))
    )
    (comp (ref "R115")
      (value "TLRZ2BTTD")
      (footprint "TLRZ2BTTD-Footprint-1")
      (description "Res Metal Plate 1206 0 Ohm Sulfur Resistant Pad SMD Automotive T/R")
      (fields (field (name "MANUFACTURER") "KOA Speer Electronics") (field (name "VALUE 2") "0R"))
      (libsource (lib "Krakul Vault") (part "RESISTOR_GENERIC_IEC"))
    )
    (comp (ref "R116")
      (value "TLRZ2BTTD")
      (footprint "TLRZ2BTTD-Footprint-1")
      (description "Res Metal Plate 1206 0 Ohm Sulfur Resistant Pad SMD Automotive T/R")
      (fields (field (name "MANUFACTURER") "KOA Speer Electronics") (field (name "VALUE 2") "0R"))
      (libsource (lib "Krakul Vault") (part "RESISTOR_GENERIC_IEC"))
    )
    (comp (ref "R117")
      (value "TLRZ2BTTD")
      (footprint "TLRZ2BTTD-Footprint-1")
      (description "Res Metal Plate 1206 0 Ohm Sulfur Resistant Pad SMD Automotive T/R")
      (fields (field (name "MANUFACTURER") "KOA Speer Electronics") (field (name "VALUE 2") "0R"))
      (libsource (lib "Krakul Vault") (part "RESISTOR_GENERIC_IEC"))
    )
    (comp (ref "R118")
      (value "100R")
      (footprint "Resistor_0603_M")
      (description "Resistor, 0603, 100R, 1%, 1/10W")
      (fields (field (name "TOLERANCE") "1%") (field (name "POWER") "100mW"))
      (libsource (lib "Krakul Vault") (part "RESISTOR_GENERIC_IEC"))
    )
    (comp (ref "R119")
      (value "100R")
      (footprint "Resistor_0603_M")
      (description "Resistor, 0603, 100R, 1%, 1/10W")
      (fields (field (name "TOLERANCE") "1%") (field (name "POWER") "100mW"))
      (libsource (lib "Krakul Vault") (part "RESISTOR_GENERIC_IEC"))
    )
    (comp (ref "R120")
      (value "10k")
      (footprint "Resistor_0603_M")
      (description "Resistor, 0603, 10k, 1%, 1/10W")
      (fields (field (name "MANUFACTURER") "Any") (field (name "TOLERANCE") "1%"))
      (libsource (lib "Krakul Vault") (part "RESISTOR_GENERIC_IEC"))
    )
    (comp (ref "R121")
      (value "10k")
      (footprint "Resistor_0603_M")
      (description "Resistor, 0603, 10k, 1%, 1/10W")
      (fields (field (name "MANUFACTURER") "Any") (field (name "TOLERANCE") "1%"))
      (libsource (lib "Krakul Vault") (part "RESISTOR_GENERIC_IEC"))
    )
    (comp (ref "R122")
      (value "100R")
      (footprint "Resistor_0603_M")
      (description "Resistor, 0603, 100R, 1%, 1/10W")
      (fields (field (name "TOLERANCE") "1%") (field (name "POWER") "100mW"))
      (libsource (lib "Krakul Vault") (part "RESISTOR_GENERIC_IEC"))
    )
    (comp (ref "R123")
      (value "10k")
      (footprint "Resistor_0603_M")
      (description "Resistor, 0603, 10k, 1%, 1/10W")
      (fields (field (name "MANUFACTURER") "Any") (field (name "TOLERANCE") "1%"))
      (libsource (lib "Krakul Vault") (part "RESISTOR_GENERIC_IEC"))
    )
    (comp (ref "R124")
      (value "TLRZ2BTTD")
      (footprint "TLRZ2BTTD-Footprint-1")
      (description "Res Metal Plate 1206 0 Ohm Sulfur Resistant Pad SMD Automotive T/R")
      (fields (field (name "MANUFACTURER") "KOA Speer Electronics") (field (name "VALUE 2") "0R"))
      (libsource (lib "Krakul Vault") (part "RESISTOR_GENERIC_IEC"))
    )
    (comp (ref "R125")
      (value "TLRZ2BTTD")
      (footprint "TLRZ2BTTD-Footprint-1")
      (description "Res Metal Plate 1206 0 Ohm Sulfur Resistant Pad SMD Automotive T/R")
      (fields (field (name "MANUFACTURER") "KOA Speer Electronics") (field (name "VALUE 2") "0R"))
      (libsource (lib "Krakul Vault") (part "RESISTOR_GENERIC_IEC"))
    )
    (comp (ref "R126")
      (value "TLRZ2BTTD")
      (footprint "TLRZ2BTTD-Footprint-1")
      (description "Res Metal Plate 1206 0 Ohm Sulfur Resistant Pad SMD Automotive T/R")
      (fields (field (name "MANUFACTURER") "KOA Speer Electronics") (field (name "VALUE 2") "0R"))
      (libsource (lib "Krakul Vault") (part "RESISTOR_GENERIC_IEC"))
    )
    (comp (ref "R127")
      (value "TLRZ2BTTD")
      (footprint "TLRZ2BTTD-Footprint-1")
      (description "Res Metal Plate 1206 0 Ohm Sulfur Resistant Pad SMD Automotive T/R")
      (fields (field (name "MANUFACTURER") "KOA Speer Electronics") (field (name "VALUE 2") "0R"))
      (libsource (lib "Krakul Vault") (part "RESISTOR_GENERIC_IEC"))
    )
    (comp (ref "R128")
      (value "100R")
      (footprint "Resistor_0603_M")
      (description "Resistor, 0603, 100R, 1%, 1/10W")
      (fields (field (name "TOLERANCE") "1%") (field (name "POWER") "100mW"))
      (libsource (lib "Krakul Vault") (part "RESISTOR_GENERIC_IEC"))
    )
    (comp (ref "R129")
      (value "10k")
      (footprint "Resistor_0603_M")
      (description "Resistor, 0603, 10k, 1%, 1/10W")
      (fields (field (name "MANUFACTURER") "Any") (field (name "TOLERANCE") "1%"))
      (libsource (lib "Krakul Vault") (part "RESISTOR_GENERIC_IEC"))
    )
    (comp (ref "R130")
      (value "100R")
      (footprint "Resistor_0603_M")
      (description "Resistor, 0603, 100R, 1%, 1/10W")
      (fields (field (name "TOLERANCE") "1%") (field (name "POWER") "100mW"))
      (libsource (lib "Krakul Vault") (part "RESISTOR_GENERIC_IEC"))
    )
    (comp (ref "R131")
      (value "10k")
      (footprint "Resistor_0603_M")
      (description "Resistor, 0603, 10k, 1%, 1/10W")
      (fields (field (name "MANUFACTURER") "Any") (field (name "TOLERANCE") "1%"))
      (libsource (lib "Krakul Vault") (part "RESISTOR_GENERIC_IEC"))
    )
    (comp (ref "R132")
      (value "10k")
      (footprint "Resistor_0603_M")
      (description "Resistor, 0603, 10k, 1%, 1/10W")
      (fields (field (name "MANUFACTURER") "Any") (field (name "TOLERANCE") "1%"))
      (libsource (lib "Krakul Vault") (part "RESISTOR_GENERIC_IEC"))
    )
    (comp (ref "R133")
      (value "10k")
      (footprint "Resistor_0603_M")
      (description "Resistor, 0603, 10k, 1%, 1/10W")
      (fields (field (name "MANUFACTURER") "Any") (field (name "TOLERANCE") "1%"))
      (libsource (lib "Krakul Vault") (part "RESISTOR_GENERIC_IEC"))
    )
    (comp (ref "R134")
      (value "10k")
      (footprint "Resistor_0603_M")
      (description "Resistor, 0603, 10k, 1%, 1/10W")
      (fields (field (name "MANUFACTURER") "Any") (field (name "TOLERANCE") "1%"))
      (libsource (lib "Krakul Vault") (part "RESISTOR_GENERIC_IEC"))
    )
    (comp (ref "R135")
      (value "1k")
      (footprint "Resistor_0603_M")
      (description "Resistor, 0603, 1k, 0.1%, 1/16W")
      (fields (field (name "MANUFACTURER") "Any"))
      (libsource (lib "Krakul Vault") (part "RESISTOR_GENERIC_IEC"))
    )
    (comp (ref "R136")
      (value "1k")
      (footprint "Resistor_0603_M")
      (description "Resistor, 0603, 1k, 0.1%, 1/16W")
      (fields (field (name "MANUFACTURER") "Any"))
      (libsource (lib "Krakul Vault") (part "RESISTOR_GENERIC_IEC"))
    )
    (comp (ref "R137")
      (value "1k")
      (footprint "Resistor_0603_M")
      (description "Resistor, 0603, 1k, 0.1%, 1/16W")
      (fields (field (name "MANUFACTURER") "Any"))
      (libsource (lib "Krakul Vault") (part "RESISTOR_GENERIC_IEC"))
    )
    (comp (ref "R138")
      (value "10k")
      (footprint "Resistor_0603_M")
      (description "Resistor, 0603, 10k, 1%, 1/10W")
      (fields (field (name "MANUFACTURER") "Any") (field (name "TOLERANCE") "1%"))
      (libsource (lib "Krakul Vault") (part "RESISTOR_GENERIC_IEC"))
    )
    (comp (ref "R139")
      (value "10k")
      (footprint "Resistor_0603_M")
      (description "Resistor, 0603, 10k, 1%, 1/10W")
      (fields (field (name "MANUFACTURER") "Any") (field (name "TOLERANCE") "1%"))
      (libsource (lib "Krakul Vault") (part "RESISTOR_GENERIC_IEC"))
    )
    (comp (ref "R140")
      (value "10k")
      (footprint "Resistor_0603_M")
      (description "Resistor, 0603, 10k, 1%, 1/10W")
      (fields (field (name "MANUFACTURER") "Any") (field (name "TOLERANCE") "1%"))
      (libsource (lib "Krakul Vault") (part "RESISTOR_GENERIC_IEC"))
    )
    (comp (ref "R141")
      (value "1k")
      (footprint "Resistor_0603_M")
      (description "Resistor, 0603, 1k, 0.1%, 1/16W")
      (fields (field (name "MANUFACTURER") "Any"))
      (libsource (lib "Krakul Vault") (part "RESISTOR_GENERIC_IEC"))
    )
    (comp (ref "R142")
      (value "1k")
      (footprint "Resistor_0603_M")
      (description "Resistor, 0603, 1k, 0.1%, 1/16W")
      (fields (field (name "MANUFACTURER") "Any"))
      (libsource (lib "Krakul Vault") (part "RESISTOR_GENERIC_IEC"))
    )
    (comp (ref "R143")
      (value "1k")
      (footprint "Resistor_0603_M")
      (description "Resistor, 0603, 1k, 0.1%, 1/16W")
      (fields (field (name "MANUFACTURER") "Any"))
      (libsource (lib "Krakul Vault") (part "RESISTOR_GENERIC_IEC"))
    )
    (comp (ref "R144")
      (value "10k")
      (footprint "Resistor_0603_M")
      (description "Resistor, 0603, 10k, 1%, 1/10W")
      (fields (field (name "MANUFACTURER") "Any") (field (name "TOLERANCE") "1%"))
      (libsource (lib "Krakul Vault") (part "RESISTOR_GENERIC_IEC"))
    )
    (comp (ref "R145")
      (value "10k")
      (footprint "Resistor_0603_M")
      (description "Resistor, 0603, 10k, 1%, 1/10W")
      (fields (field (name "MANUFACTURER") "Any") (field (name "TOLERANCE") "1%"))
      (libsource (lib "Krakul Vault") (part "RESISTOR_GENERIC_IEC"))
    )
    (comp (ref "R146")
      (value "1k")
      (footprint "Resistor_0603_M")
      (description "Resistor, 0603, 1k, 0.1%, 1/16W")
      (fields (field (name "MANUFACTURER") "Any"))
      (libsource (lib "Krakul Vault") (part "RESISTOR_GENERIC_IEC"))
    )
    (comp (ref "R147")
      (value "1k")
      (footprint "Resistor_0603_M")
      (description "Resistor, 0603, 1k, 0.1%, 1/16W")
      (fields (field (name "MANUFACTURER") "Any"))
      (libsource (lib "Krakul Vault") (part "RESISTOR_GENERIC_IEC"))
    )
    (comp (ref "R148")
      (value "0.05R")
      (footprint "0805 resisitor based on RCWE080550L0FNEA")
      (description "SMD Chip Resistor, 50 MOhm, ± 1%, 250 mW, 0805 [2012 Metric], Thick Film, Anti-Sulfur")
      (fields (field (name "MANUFACTURER") "Any") (field (name "PART NUMBER") "RCWE080550L0FNEA"))
      (libsource (lib "Krakul Vault") (part "RESISTOR_GENERIC_IEC"))
    )
    (comp (ref "R149")
      (value "0.05R")
      (footprint "0805 resisitor based on RCWE080550L0FNEA")
      (description "SMD Chip Resistor, 50 MOhm, ± 1%, 250 mW, 0805 [2012 Metric], Thick Film, Anti-Sulfur")
      (fields (field (name "MANUFACTURER") "Any") (field (name "PART NUMBER") "RCWE080550L0FNEA"))
      (libsource (lib "Krakul Vault") (part "RESISTOR_GENERIC_IEC"))
    )
    (comp (ref "R150")
      (value "0.05R")
      (footprint "0805 resisitor based on RCWE080550L0FNEA")
      (description "SMD Chip Resistor, 50 MOhm, ± 1%, 250 mW, 0805 [2012 Metric], Thick Film, Anti-Sulfur")
      (fields (field (name "MANUFACTURER") "Any") (field (name "PART NUMBER") "RCWE080550L0FNEA"))
      (libsource (lib "Krakul Vault") (part "RESISTOR_GENERIC_IEC"))
    )
    (comp (ref "R151")
      (value "0.05R")
      (footprint "0805 resisitor based on RCWE080550L0FNEA")
      (description "SMD Chip Resistor, 50 MOhm, ± 1%, 250 mW, 0805 [2012 Metric], Thick Film, Anti-Sulfur")
      (fields (field (name "MANUFACTURER") "Any") (field (name "PART NUMBER") "RCWE080550L0FNEA"))
      (libsource (lib "Krakul Vault") (part "RESISTOR_GENERIC_IEC"))
    )
    (comp (ref "R152")
      (value "0.05R")
      (footprint "0805 resisitor based on RCWE080550L0FNEA")
      (description "SMD Chip Resistor, 50 MOhm, ± 1%, 250 mW, 0805 [2012 Metric], Thick Film, Anti-Sulfur")
      (fields (field (name "MANUFACTURER") "Any") (field (name "PART NUMBER") "RCWE080550L0FNEA"))
      (libsource (lib "Krakul Vault") (part "RESISTOR_GENERIC_IEC"))
    )
    (comp (ref "R153")
      (value "0.05R")
      (footprint "0805 resisitor based on RCWE080550L0FNEA")
      (description "SMD Chip Resistor, 50 MOhm, ± 1%, 250 mW, 0805 [2012 Metric], Thick Film, Anti-Sulfur")
      (fields (field (name "MANUFACTURER") "Any") (field (name "PART NUMBER") "RCWE080550L0FNEA"))
      (libsource (lib "Krakul Vault") (part "RESISTOR_GENERIC_IEC"))
    )
    (comp (ref "R154")
      (value "0.05R")
      (footprint "0805 resisitor based on RCWE080550L0FNEA")
      (description "SMD Chip Resistor, 50 MOhm, ± 1%, 250 mW, 0805 [2012 Metric], Thick Film, Anti-Sulfur")
      (fields (field (name "MANUFACTURER") "Any") (field (name "PART NUMBER") "RCWE080550L0FNEA"))
      (libsource (lib "Krakul Vault") (part "RESISTOR_GENERIC_IEC"))
    )
    (comp (ref "R155")
      (value "0.05R")
      (footprint "0805 resisitor based on RCWE080550L0FNEA")
      (description "SMD Chip Resistor, 50 MOhm, ± 1%, 250 mW, 0805 [2012 Metric], Thick Film, Anti-Sulfur")
      (fields (field (name "MANUFACTURER") "Any") (field (name "PART NUMBER") "RCWE080550L0FNEA"))
      (libsource (lib "Krakul Vault") (part "RESISTOR_GENERIC_IEC"))
    )
    (comp (ref "TP100")
      (value "Testpoint 1mm")
      (footprint "Testpoint 1mm")
      (libsource (lib "Krakul Vault") (part "Testpoint"))
    )
    (comp (ref "TP101")
      (value "Testpoint 1mm")
      (footprint "Testpoint 1mm")
      (libsource (lib "Krakul Vault") (part "Testpoint"))
    )
    (comp (ref "TP102")
      (value "Testpoint 1mm")
      (footprint "Testpoint 1mm")
      (libsource (lib "Krakul Vault") (part "Testpoint"))
    )
    (comp (ref "TP103")
      (value "Testpoint 1mm")
      (footprint "Testpoint 1mm")
      (libsource (lib "Krakul Vault") (part "Testpoint"))
    )
    (comp (ref "TP104")
      (value "Testpoint 1mm")
      (footprint "Testpoint 1mm")
      (libsource (lib "Krakul Vault") (part "Testpoint"))
    )
    (comp (ref "TP105")
      (value "Testpoint 1mm")
      (footprint "Testpoint 1mm")
      (libsource (lib "Krakul Vault") (part "Testpoint"))
    )
    (comp (ref "TP106")
      (value "Testpoint 1mm")
      (footprint "Testpoint 1mm")
      (libsource (lib "Krakul Vault") (part "Testpoint"))
    )
    (comp (ref "TP107")
      (value "Testpoint 1mm")
      (footprint "Testpoint 1mm")
      (libsource (lib "Krakul Vault") (part "Testpoint"))
    )
  )
  (nets
    (net (code "1") (name "+3V3_AN") (class "Default")
      (node (ref "C116") (pin "2") (pinfunction "2_2") (pintype "passive"))
      (node (ref "C117") (pin "2") (pinfunction "2_2") (pintype "passive"))
      (node (ref "C118") (pin "2") (pinfunction "2_2") (pintype "passive"))
      (node (ref "C119") (pin "2") (pinfunction "2_2") (pintype "passive"))
      (node (ref "C120") (pin "2") (pinfunction "2_2") (pintype "passive"))
      (node (ref "C121") (pin "2") (pinfunction "2_2") (pintype "passive"))
      (node (ref "C122") (pin "2") (pinfunction "2_2") (pintype "passive"))
      (node (ref "C123") (pin "2") (pinfunction "2_2") (pintype "passive"))
      (node (ref "D111") (pin "2") (pinfunction "2_2") (pintype "passive"))
      (node (ref "D112") (pin "2") (pinfunction "2_2") (pintype "passive"))
      (node (ref "D113") (pin "2") (pinfunction "2_2") (pintype "passive"))
      (node (ref "D117") (pin "2") (pinfunction "2_2") (pintype "passive"))
      (node (ref "D118") (pin "2") (pinfunction "2_2") (pintype "passive"))
      (node (ref "D119") (pin "2") (pinfunction "2_2") (pintype "passive"))
      (node (ref "D122") (pin "2") (pinfunction "2_2") (pintype "passive"))
      (node (ref "D123") (pin "2") (pinfunction "2_2") (pintype "passive"))
    )
    (net (code "2") (name "/OUT_1_EN") (class "Default")
      (node (ref "R106") (pin "1") (pinfunction "1_1") (pintype "passive"))
    )
    (net (code "3") (name "/OUT_1_PWR") (class "Default")
      (node (ref "R100") (pin "2") (pinfunction "2_2") (pintype "passive"))
      (node (ref "R101") (pin "2") (pinfunction "2_2") (pintype "passive"))
    )
    (net (code "4") (name "/OUT_1_SNUB") (class "Default")
      (node (ref "C124") (pin "2") (pinfunction "2_2") (pintype "passive"))
      (node (ref "C125") (pin "2") (pinfunction "2_2") (pintype "passive"))
      (node (ref "C126") (pin "2") (pinfunction "2_2") (pintype "passive"))
      (node (ref "F100") (pin "1") (pinfunction "1_1") (pintype "passive"))
      (node (ref "F100") (pin "2") (pinfunction "1_2") (pintype "passive"))
      (node (ref "K100") (pin "1") (pinfunction "COM_1") (pintype "passive"))
    )
    (net (code "5") (name "/OUT_1_V") (class "Default")
      (node (ref "C104") (pin "2") (pinfunction "2_2") (pintype "passive"))
      (node (ref "D112") (pin "3") (pinfunction "3_3") (pintype "passive"))
      (node (ref "R133") (pin "1") (pinfunction "1_1") (pintype "passive"))
      (node (ref "R136") (pin "2") (pinfunction "2_2") (pintype "passive"))
    )
    (net (code "6") (name "/OUT_2_EN") (class "Default")
      (node (ref "R107") (pin "1") (pinfunction "1_1") (pintype "passive"))
    )
    (net (code "7") (name "/OUT_2_PWR") (class "Default")
      (node (ref "R102") (pin "2") (pinfunction "2_2") (pintype "passive"))
      (node (ref "R103") (pin "2") (pinfunction "2_2") (pintype "passive"))
    )
    (net (code "8") (name "/OUT_2_SNUB") (class "Default")
      (node (ref "C130") (pin "2") (pinfunction "2_2") (pintype "passive"))
      (node (ref "C131") (pin "2") (pinfunction "2_2") (pintype "passive"))
      (node (ref "C132") (pin "2") (pinfunction "2_2") (pintype "passive"))
      (node (ref "F101") (pin "1") (pinfunction "1_1") (pintype "passive"))
      (node (ref "F101") (pin "2") (pinfunction "1_2") (pintype "passive"))
      (node (ref "K101") (pin "1") (pinfunction "COM_1") (pintype "passive"))
    )
    (net (code "9") (name "/OUT_2_V") (class "Default")
      (node (ref "C105") (pin "2") (pinfunction "2_2") (pintype "passive"))
      (node (ref "D113") (pin "3") (pinfunction "3_3") (pintype "passive"))
      (node (ref "R134") (pin "1") (pinfunction "1_1") (pintype "passive"))
      (node (ref "R137") (pin "2") (pinfunction "2_2") (pintype "passive"))
    )
    (net (code "10") (name "/OUT_3_EN") (class "Default")
      (node (ref "R109") (pin "1") (pinfunction "1_1") (pintype "passive"))
    )
    (net (code "11") (name "/OUT_3_PWR") (class "Default")
      (node (ref "R104") (pin "2") (pinfunction "2_2") (pintype "passive"))
      (node (ref "R105") (pin "2") (pinfunction "2_2") (pintype "passive"))
    )
    (net (code "12") (name "/OUT_3_SNUB") (class "Default")
      (node (ref "C127") (pin "2") (pinfunction "2_2") (pintype "passive"))
      (node (ref "C128") (pin "2") (pinfunction "2_2") (pintype "passive"))
      (node (ref "C129") (pin "2") (pinfunction "2_2") (pintype "passive"))
      (node (ref "F102") (pin "1") (pinfunction "1_1") (pintype "passive"))
      (node (ref "F102") (pin "2") (pinfunction "1_2") (pintype "passive"))
      (node (ref "K102") (pin "1") (pinfunction "COM_1") (pintype "passive"))
    )
    (net (code "13") (name "/OUT_3_V") (class "Default")
      (node (ref "C103") (pin "2") (pinfunction "2_2") (pintype "passive"))
      (node (ref "D111") (pin "3") (pinfunction "3_3") (pintype "passive"))
      (node (ref "R132") (pin "1") (pinfunction "1_1") (pintype "passive"))
      (node (ref "R135") (pin "2") (pinfunction "2_2") (pintype "passive"))
    )
    (net (code "14") (name "/OUT_4_EN") (class "Default")
      (node (ref "R118") (pin "1") (pinfunction "1_1") (pintype "passive"))
    )
    (net (code "15") (name "/OUT_4_PWR") (class "Default")
      (node (ref "R112") (pin "2") (pinfunction "2_2") (pintype "passive"))
      (node (ref "R113") (pin "2") (pinfunction "2_2") (pintype "passive"))
    )
    (net (code "16") (name "/OUT_4_SNUB") (class "Default")
      (node (ref "C133") (pin "2") (pinfunction "2_2") (pintype "passive"))
      (node (ref "C134") (pin "2") (pinfunction "2_2") (pintype "passive"))
      (node (ref "C135") (pin "2") (pinfunction "2_2") (pintype "passive"))
      (node (ref "F103") (pin "1") (pinfunction "1_1") (pintype "passive"))
      (node (ref "F103") (pin "2") (pinfunction "1_2") (pintype "passive"))
      (node (ref "K103") (pin "1") (pinfunction "COM_1") (pintype "passive"))
    )
    (net (code "17") (name "/OUT_4_V") (class "Default")
      (node (ref "C109") (pin "2") (pinfunction "2_2") (pintype "passive"))
      (node (ref "D117") (pin "3") (pinfunction "3_3") (pintype "passive"))
      (node (ref "R138") (pin "1") (pinfunction "1_1") (pintype "passive"))
      (node (ref "R141") (pin "2") (pinfunction "2_2") (pintype "passive"))
    )
    (net (code "18") (name "/OUT_5_EN") (class "Default")
      (node (ref "R119") (pin "1") (pinfunction "1_1") (pintype "passive"))
    )
    (net (code "19") (name "/OUT_5_PWR") (class "Default")
      (node (ref "R114") (pin "2") (pinfunction "2_2") (pintype "passive"))
      (node (ref "R115") (pin "2") (pinfunction "2_2") (pintype "passive"))
    )
    (net (code "20") (name "/OUT_5_SNUB") (class "Default")
      (node (ref "C136") (pin "2") (pinfunction "2_2") (pintype "passive"))
      (node (ref "C137") (pin "2") (pinfunction "2_2") (pintype "passive"))
      (node (ref "C138") (pin "2") (pinfunction "2_2") (pintype "passive"))
      (node (ref "F104") (pin "1") (pinfunction "1_1") (pintype "passive"))
      (node (ref "F104") (pin "2") (pinfunction "1_2") (pintype "passive"))
      (node (ref "K104") (pin "1") (pinfunction "COM_1") (pintype "passive"))
    )
    (net (code "21") (name "/OUT_5_V") (class "Default")
      (node (ref "C110") (pin "2") (pinfunction "2_2") (pintype "passive"))
      (node (ref "D118") (pin "3") (pinfunction "3_3") (pintype "passive"))
      (node (ref "R139") (pin "1") (pinfunction "1_1") (pintype "passive"))
      (node (ref "R142") (pin "2") (pinfunction "2_2") (pintype "passive"))
    )
    (net (code "22") (name "/OUT_6_EN") (class "Default")
      (node (ref "R122") (pin "1") (pinfunction "1_1") (pintype "passive"))
    )
    (net (code "23") (name "/OUT_6_PWR") (class "Default")
      (node (ref "R116") (pin "2") (pinfunction "2_2") (pintype "passive"))
      (node (ref "R117") (pin "2") (pinfunction "2_2") (pintype "passive"))
    )
    (net (code "24") (name "/OUT_6_SNUB") (class "Default")
      (node (ref "C139") (pin "2") (pinfunction "2_2") (pintype "passive"))
      (node (ref "C140") (pin "2") (pinfunction "2_2") (pintype "passive"))
      (node (ref "C141") (pin "2") (pinfunction "2_2") (pintype "passive"))
      (node (ref "F105") (pin "1") (pinfunction "1_1") (pintype "passive"))
      (node (ref "F105") (pin "2") (pinfunction "1_2") (pintype "passive"))
      (node (ref "K105") (pin "1") (pinfunction "COM_1") (pintype "passive"))
    )
    (net (code "25") (name "/OUT_6_V") (class "Default")
      (node (ref "C111") (pin "2") (pinfunction "2_2") (pintype "passive"))
      (node (ref "D119") (pin "3") (pinfunction "3_3") (pintype "passive"))
      (node (ref "R140") (pin "1") (pinfunction "1_1") (pintype "passive"))
      (node (ref "R143") (pin "2") (pinfunction "2_2") (pintype "passive"))
    )
    (net (code "26") (name "/OUT_7_EN") (class "Default")
      (node (ref "R128") (pin "1") (pinfunction "1_1") (pintype "passive"))
    )
    (net (code "27") (name "/OUT_7_PWR") (class "Default")
      (node (ref "R124") (pin "2") (pinfunction "2_2") (pintype "passive"))
      (node (ref "R125") (pin "2") (pinfunction "2_2") (pintype "passive"))
    )
    (net (code "28") (name "/OUT_7_SNUB") (class "Default")
      (node (ref "C142") (pin "2") (pinfunction "2_2") (pintype "passive"))
      (node (ref "C143") (pin "2") (pinfunction "2_2") (pintype "passive"))
      (node (ref "C144") (pin "2") (pinfunction "2_2") (pintype "passive"))
      (node (ref "F106") (pin "1") (pinfunction "1_1") (pintype "passive"))
      (node (ref "F106") (pin "2") (pinfunction "1_2") (pintype "passive"))
      (node (ref "K106") (pin "1") (pinfunction "COM_1") (pintype "passive"))
    )
    (net (code "29") (name "/OUT_7_V") (class "Default")
      (node (ref "C114") (pin "2") (pinfunction "2_2") (pintype "passive"))
      (node (ref "D122") (pin "3") (pinfunction "3_3") (pintype "passive"))
      (node (ref "R144") (pin "1") (pinfunction "1_1") (pintype "passive"))
      (node (ref "R146") (pin "2") (pinfunction "2_2") (pintype "passive"))
    )
    (net (code "30") (name "/OUT_8_EN") (class "Default")
      (node (ref "R130") (pin "1") (pinfunction "1_1") (pintype "passive"))
    )
    (net (code "31") (name "/OUT_8_PWR") (class "Default")
      (node (ref "R126") (pin "2") (pinfunction "2_2") (pintype "passive"))
      (node (ref "R127") (pin "2") (pinfunction "2_2") (pintype "passive"))
    )
    (net (code "32") (name "/OUT_8_SNUB") (class "Default")
      (node (ref "C145") (pin "2") (pinfunction "2_2") (pintype "passive"))
      (node (ref "C146") (pin "2") (pinfunction "2_2") (pintype "passive"))
      (node (ref "C147") (pin "2") (pinfunction "2_2") (pintype "passive"))
      (node (ref "F107") (pin "1") (pinfunction "1_1") (pintype "passive"))
      (node (ref "F107") (pin "2") (pinfunction "1_2") (pintype "passive"))
      (node (ref "K107") (pin "1") (pinfunction "COM_1") (pintype "passive"))
    )
    (net (code "33") (name "/OUT_8_V") (class "Default")
      (node (ref "C115") (pin "2") (pinfunction "2_2") (pintype "passive"))
      (node (ref "D123") (pin "3") (pinfunction "3_3") (pintype "passive"))
      (node (ref "R145") (pin "1") (pinfunction "1_1") (pintype "passive"))
      (node (ref "R147") (pin "2") (pinfunction "2_2") (pintype "passive"))
    )
    (net (code "34") (name "GND") (class "Default")
      (node (ref "C100") (pin "1") (pinfunction "1_1") (pintype "passive"))
      (node (ref "C101") (pin "1") (pinfunction "1_1") (pintype "passive"))
      (node (ref "C102") (pin "1") (pinfunction "1_1") (pintype "passive"))
      (node (ref "C103") (pin "1") (pinfunction "1_1") (pintype "passive"))
      (node (ref "C104") (pin "1") (pinfunction "1_1") (pintype "passive"))
      (node (ref "C105") (pin "1") (pinfunction "1_1") (pintype "passive"))
      (node (ref "C106") (pin "1") (pinfunction "1_1") (pintype "passive"))
      (node (ref "C107") (pin "1") (pinfunction "1_1") (pintype "passive"))
      (node (ref "C108") (pin "1") (pinfunction "1_1") (pintype "passive"))
      (node (ref "C109") (pin "1") (pinfunction "1_1") (pintype "passive"))
      (node (ref "C110") (pin "1") (pinfunction "1_1") (pintype "passive"))
      (node (ref "C111") (pin "1") (pinfunction "1_1") (pintype "passive"))
      (node (ref "C112") (pin "1") (pinfunction "1_1") (pintype "passive"))
      (node (ref "C113") (pin "1") (pinfunction "1_1") (pintype "passive"))
      (node (ref "C114") (pin "1") (pinfunction "1_1") (pintype "passive"))
      (node (ref "C115") (pin "1") (pinfunction "1_1") (pintype "passive"))
      (node (ref "C116") (pin "1") (pinfunction "1_1") (pintype "passive"))
      (node (ref "C117") (pin "1") (pinfunction "1_1") (pintype "passive"))
      (node (ref "C118") (pin "1") (pinfunction "1_1") (pintype "passive"))
      (node (ref "C119") (pin "1") (pinfunction "1_1") (pintype "passive"))
      (node (ref "C120") (pin "1") (pinfunction "1_1") (pintype "passive"))
      (node (ref "C121") (pin "1") (pinfunction "1_1") (pintype "passive"))
      (node (ref "C122") (pin "1") (pinfunction "1_1") (pintype "passive"))
      (node (ref "C123") (pin "1") (pinfunction "1_1") (pintype "passive"))
      (node (ref "D100") (pin "2") (pinfunction "A_2") (pintype "passive"))
      (node (ref "D101") (pin "2") (pinfunction "A_2") (pintype "passive"))
      (node (ref "D102") (pin "2") (pinfunction "A_2") (pintype "passive"))
      (node (ref "D103") (pin "2") (pinfunction "A_2") (pintype "passive"))
      (node (ref "D104") (pin "2") (pinfunction "A_2") (pintype "passive"))
      (node (ref "D105") (pin "2") (pinfunction "A_2") (pintype "passive"))
      (node (ref "D106") (pin "2") (pinfunction "A_2") (pintype "passive"))
      (node (ref "D107") (pin "2") (pinfunction "A_2") (pintype "passive"))
      (node (ref "D108") (pin "2") (pinfunction "A_2") (pintype "passive"))
      (node (ref "D109") (pin "2") (pinfunction "A_2") (pintype "passive"))
      (node (ref "D110") (pin "2") (pinfunction "A_2") (pintype "passive"))
      (node (ref "D111") (pin "1") (pinfunction "1_1") (pintype "passive"))
      (node (ref "D112") (pin "1") (pinfunction "1_1") (pintype "passive"))
      (node (ref "D113") (pin "1") (pinfunction "1_1") (pintype "passive"))
      (node (ref "D114") (pin "2") (pinfunction "A_2") (pintype "passive"))
      (node (ref "D115") (pin "2") (pinfunction "A_2") (pintype "passive"))
      (node (ref "D116") (pin "2") (pinfunction "A_2") (pintype "passive"))
      (node (ref "D117") (pin "1") (pinfunction "1_1") (pintype "passive"))
      (node (ref "D118") (pin "1") (pinfunction "1_1") (pintype "passive"))
      (node (ref "D119") (pin "1") (pinfunction "1_1") (pintype "passive"))
      (node (ref "D120") (pin "2") (pinfunction "A_2") (pintype "passive"))
      (node (ref "D121") (pin "2") (pinfunction "A_2") (pintype "passive"))
      (node (ref "D122") (pin "1") (pinfunction "1_1") (pintype "passive"))
      (node (ref "D123") (pin "1") (pinfunction "1_1") (pintype "passive"))
      (node (ref "P100") (pin "2") (pinfunction "2_2") (pintype "passive"))
      (node (ref "P101") (pin "2") (pinfunction "2_2") (pintype "passive"))
      (node (ref "P102") (pin "2") (pinfunction "2_2") (pintype "passive"))
      (node (ref "P103") (pin "2") (pinfunction "2_2") (pintype "passive"))
      (node (ref "P104") (pin "2") (pinfunction "2_2") (pintype "passive"))
      (node (ref "P105") (pin "2") (pinfunction "2_2") (pintype "passive"))
      (node (ref "P106") (pin "2") (pinfunction "2_2") (pintype "passive"))
      (node (ref "P107") (pin "2") (pinfunction "2_2") (pintype "passive"))
      (node (ref "Q100") (pin "2") (pinfunction "S_2") (pintype "passive"))
      (node (ref "Q101") (pin "2") (pinfunction "S_2") (pintype "passive"))
      (node (ref "Q102") (pin "2") (pinfunction "S_2") (pintype "passive"))
      (node (ref "Q103") (pin "2") (pinfunction "S_2") (pintype "passive"))
      (node (ref "Q104") (pin "2") (pinfunction "S_2") (pintype "passive"))
      (node (ref "Q105") (pin "2") (pinfunction "S_2") (pintype "passive"))
      (node (ref "Q106") (pin "2") (pinfunction "S_2") (pintype "passive"))
      (node (ref "Q107") (pin "2") (pinfunction "S_2") (pintype "passive"))
      (node (ref "R108") (pin "1") (pinfunction "1_1") (pintype "passive"))
      (node (ref "R110") (pin "1") (pinfunction "1_1") (pintype "passive"))
      (node (ref "R111") (pin "1") (pinfunction "1_1") (pintype "passive"))
      (node (ref "R120") (pin "1") (pinfunction "1_1") (pintype "passive"))
      (node (ref "R121") (pin "1") (pinfunction "1_1") (pintype "passive"))
      (node (ref "R123") (pin "1") (pinfunction "1_1") (pintype "passive"))
      (node (ref "R129") (pin "1") (pinfunction "1_1") (pintype "passive"))
      (node (ref "R131") (pin "1") (pinfunction "1_1") (pintype "passive"))
      (node (ref "R135") (pin "1") (pinfunction "1_1") (pintype "passive"))
      (node (ref "R136") (pin "1") (pinfunction "1_1") (pintype "passive"))
      (node (ref "R137") (pin "1") (pinfunction "1_1") (pintype "passive"))
      (node (ref "R141") (pin "1") (pinfunction "1_1") (pintype "passive"))
      (node (ref "R142") (pin "1") (pinfunction "1_1") (pintype "passive"))
      (node (ref "R143") (pin "1") (pinfunction "1_1") (pintype "passive"))
      (node (ref "R146") (pin "1") (pinfunction "1_1") (pintype "passive"))
      (node (ref "R147") (pin "1") (pinfunction "1_1") (pintype "passive"))
      (node (ref "R148") (pin "1") (pinfunction "1_1") (pintype "passive"))
      (node (ref "R149") (pin "1") (pinfunction "1_1") (pintype "passive"))
      (node (ref "R150") (pin "1") (pinfunction "1_1") (pintype "passive"))
      (node (ref "R151") (pin "1") (pinfunction "1_1") (pintype "passive"))
      (node (ref "R152") (pin "1") (pinfunction "1_1") (pintype "passive"))
      (node (ref "R153") (pin "1") (pinfunction "1_1") (pintype "passive"))
      (node (ref "R154") (pin "1") (pinfunction "1_1") (pintype "passive"))
      (node (ref "R155") (pin "1") (pinfunction "1_1") (pintype "passive"))
    )
    (net (code "35") (name "Net-(C124-Pad1)") (class "Default")
      (node (ref "C124") (pin "1") (pinfunction "1_1") (pintype "passive"))
      (node (ref "C125") (pin "1") (pinfunction "1_1") (pintype "passive"))
      (node (ref "C126") (pin "1") (pinfunction "1_1") (pintype "passive"))
      (node (ref "R148") (pin "2") (pinfunction "2_2") (pintype "passive"))
    )
    (net (code "36") (name "Net-(C127-Pad1)") (class "Default")
      (node (ref "C127") (pin "1") (pinfunction "1_1") (pintype "passive"))
      (node (ref "C128") (pin "1") (pinfunction "1_1") (pintype "passive"))
      (node (ref "C129") (pin "1") (pinfunction "1_1") (pintype "passive"))
      (node (ref "R149") (pin "2") (pinfunction "2_2") (pintype "passive"))
    )
    (net (code "37") (name "Net-(C130-Pad1)") (class "Default")
      (node (ref "C130") (pin "1") (pinfunction "1_1") (pintype "passive"))
      (node (ref "C131") (pin "1") (pinfunction "1_1") (pintype "passive"))
      (node (ref "C132") (pin "1") (pinfunction "1_1") (pintype "passive"))
      (node (ref "R150") (pin "2") (pinfunction "2_2") (pintype "passive"))
    )
    (net (code "38") (name "Net-(C133-Pad1)") (class "Default")
      (node (ref "C133") (pin "1") (pinfunction "1_1") (pintype "passive"))
      (node (ref "C134") (pin "1") (pinfunction "1_1") (pintype "passive"))
      (node (ref "C135") (pin "1") (pinfunction "1_1") (pintype "passive"))
      (node (ref "R151") (pin "2") (pinfunction "2_2") (pintype "passive"))
    )
    (net (code "39") (name "Net-(C136-Pad1)") (class "Default")
      (node (ref "C136") (pin "1") (pinfunction "1_1") (pintype "passive"))
      (node (ref "C137") (pin "1") (pinfunction "1_1") (pintype "passive"))
      (node (ref "C138") (pin "1") (pinfunction "1_1") (pintype "passive"))
      (node (ref "R152") (pin "2") (pinfunction "2_2") (pintype "passive"))
    )
    (net (code "40") (name "Net-(C139-Pad1)") (class "Default")
      (node (ref "C139") (pin "1") (pinfunction "1_1") (pintype "passive"))
      (node (ref "C140") (pin "1") (pinfunction "1_1") (pintype "passive"))
      (node (ref "C141") (pin "1") (pinfunction "1_1") (pintype "passive"))
      (node (ref "R153") (pin "2") (pinfunction "2_2") (pintype "passive"))
    )
    (net (code "41") (name "Net-(C142-Pad1)") (class "Default")
      (node (ref "C142") (pin "1") (pinfunction "1_1") (pintype "passive"))
      (node (ref "C143") (pin "1") (pinfunction "1_1") (pintype "passive"))
      (node (ref "C144") (pin "1") (pinfunction "1_1") (pintype "passive"))
      (node (ref "R154") (pin "2") (pinfunction "2_2") (pintype "passive"))
    )
    (net (code "42") (name "Net-(C145-Pad1)") (class "Default")
      (node (ref "C145") (pin "1") (pinfunction "1_1") (pintype "passive"))
      (node (ref "C146") (pin "1") (pinfunction "1_1") (pintype "passive"))
      (node (ref "C147") (pin "1") (pinfunction "1_1") (pintype "passive"))
      (node (ref "R155") (pin "2") (pinfunction "2_2") (pintype "passive"))
    )
    (net (code "43") (name "Net-(D100-C)") (class "Default")
      (node (ref "D100") (pin "1") (pinfunction "C_1") (pintype "passive"))
      (node (ref "K100") (pin "4") (pinfunction "COIL1_4") (pintype "passive"))
      (node (ref "Q100") (pin "3") (pinfunction "D_3") (pintype "passive"))
    )
    (net (code "44") (name "Net-(D101-C)") (class "Default")
      (node (ref "D101") (pin "1") (pinfunction "C_1") (pintype "passive"))
      (node (ref "K101") (pin "4") (pinfunction "COIL1_4") (pintype "passive"))
      (node (ref "Q101") (pin "3") (pinfunction "D_3") (pintype "passive"))
    )
    (net (code "45") (name "Net-(D102-C)") (class "Default")
      (node (ref "D102") (pin "1") (pinfunction "C_1") (pintype "passive"))
      (node (ref "K102") (pin "4") (pinfunction "COIL1_4") (pintype "passive"))
      (node (ref "Q102") (pin "3") (pinfunction "D_3") (pintype "passive"))
    )
    (net (code "46") (name "Net-(D103-C)") (class "Default")
      (node (ref "D103") (pin "1") (pinfunction "C_1") (pintype "passive"))
      (node (ref "K103") (pin "4") (pinfunction "COIL1_4") (pintype "passive"))
      (node (ref "Q104") (pin "3") (pinfunction "D_3") (pintype "passive"))
    )
    (net (code "47") (name "Net-(D104-C)") (class "Default")
      (node (ref "D104") (pin "1") (pinfunction "C_1") (pintype "passive"))
      (node (ref "K104") (pin "4") (pinfunction "COIL1_4") (pintype "passive"))
      (node (ref "Q103") (pin "3") (pinfunction "D_3") (pintype "passive"))
    )
    (net (code "48") (name "Net-(D105-C)") (class "Default")
      (node (ref "D105") (pin "1") (pinfunction "C_1") (pintype "passive"))
      (node (ref "K105") (pin "4") (pinfunction "COIL1_4") (pintype "passive"))
      (node (ref "Q105") (pin "3") (pinfunction "D_3") (pintype "passive"))
    )
    (net (code "49") (name "Net-(D106-C)") (class "Default")
      (node (ref "D106") (pin "1") (pinfunction "C_1") (pintype "passive"))
      (node (ref "K106") (pin "4") (pinfunction "COIL1_4") (pintype "passive"))
      (node (ref "Q106") (pin "3") (pinfunction "D_3") (pintype "passive"))
    )
    (net (code "50") (name "Net-(D107-C)") (class "Default")
      (node (ref "D107") (pin "1") (pinfunction "C_1") (pintype "passive"))
      (node (ref "K107") (pin "4") (pinfunction "COIL1_4") (pintype "passive"))
      (node (ref "Q107") (pin "3") (pinfunction "D_3") (pintype "passive"))
    )
    (net (code "51") (name "Net-(D108-C)") (class "Default")
      (node (ref "C100") (pin "2") (pinfunction "2_2") (pintype "passive"))
      (node (ref "D108") (pin "1") (pinfunction "C_1") (pintype "passive"))
      (node (ref "F100") (pin "3") (pinfunction "2_3") (pintype "passive"))
      (node (ref "F100") (pin "4") (pinfunction "2_4") (pintype "passive"))
      (node (ref "P100") (pin "1") (pinfunction "1_1") (pintype "passive"))
      (node (ref "R133") (pin "2") (pinfunction "2_2") (pintype "passive"))
      (node (ref "TP100") (pin "1") (pinfunction "1_1") (pintype "passive"))
    )
    (net (code "52") (name "Net-(D109-C)") (class "Default")
      (node (ref "C101") (pin "2") (pinfunction "2_2") (pintype "passive"))
      (node (ref "D109") (pin "1") (pinfunction "C_1") (pintype "passive"))
      (node (ref "F101") (pin "3") (pinfunction "2_3") (pintype "passive"))
      (node (ref "F101") (pin "4") (pinfunction "2_4") (pintype "passive"))
      (node (ref "P101") (pin "1") (pinfunction "1_1") (pintype "passive"))
      (node (ref "R134") (pin "2") (pinfunction "2_2") (pintype "passive"))
      (node (ref "TP102") (pin "1") (pinfunction "1_1") (pintype "passive"))
    )
    (net (code "53") (name "Net-(D110-C)") (class "Default")
      (node (ref "C102") (pin "2") (pinfunction "2_2") (pintype "passive"))
      (node (ref "D110") (pin "1") (pinfunction "C_1") (pintype "passive"))
      (node (ref "F102") (pin "3") (pinfunction "2_3") (pintype "passive"))
      (node (ref "F102") (pin "4") (pinfunction "2_4") (pintype "passive"))
      (node (ref "P102") (pin "1") (pinfunction "1_1") (pintype "passive"))
      (node (ref "R132") (pin "2") (pinfunction "2_2") (pintype "passive"))
      (node (ref "TP101") (pin "1") (pinfunction "1_1") (pintype "passive"))
    )
    (net (code "54") (name "Net-(D114-C)") (class "Default")
      (node (ref "C106") (pin "2") (pinfunction "2_2") (pintype "passive"))
      (node (ref "D114") (pin "1") (pinfunction "C_1") (pintype "passive"))
      (node (ref "F103") (pin "3") (pinfunction "2_3") (pintype "passive"))
      (node (ref "F103") (pin "4") (pinfunction "2_4") (pintype "passive"))
      (node (ref "P103") (pin "1") (pinfunction "1_1") (pintype "passive"))
      (node (ref "R138") (pin "2") (pinfunction "2_2") (pintype "passive"))
      (node (ref "TP104") (pin "1") (pinfunction "1_1") (pintype "passive"))
    )
    (net (code "55") (name "Net-(D115-C)") (class "Default")
      (node (ref "C107") (pin "2") (pinfunction "2_2") (pintype "passive"))
      (node (ref "D115") (pin "1") (pinfunction "C_1") (pintype "passive"))
      (node (ref "F104") (pin "3") (pinfunction "2_3") (pintype "passive"))
      (node (ref "F104") (pin "4") (pinfunction "2_4") (pintype "passive"))
      (node (ref "P104") (pin "1") (pinfunction "1_1") (pintype "passive"))
      (node (ref "R139") (pin "2") (pinfunction "2_2") (pintype "passive"))
      (node (ref "TP105") (pin "1") (pinfunction "1_1") (pintype "passive"))
    )
    (net (code "56") (name "Net-(D116-C)") (class "Default")
      (node (ref "C108") (pin "2") (pinfunction "2_2") (pintype "passive"))
      (node (ref "D116") (pin "1") (pinfunction "C_1") (pintype "passive"))
      (node (ref "F105") (pin "3") (pinfunction "2_3") (pintype "passive"))
      (node (ref "F105") (pin "4") (pinfunction "2_4") (pintype "passive"))
      (node (ref "P105") (pin "1") (pinfunction "1_1") (pintype "passive"))
      (node (ref "R140") (pin "2") (pinfunction "2_2") (pintype "passive"))
      (node (ref "TP103") (pin "1") (pinfunction "1_1") (pintype "passive"))
    )
    (net (code "57") (name "Net-(D120-C)") (class "Default")
      (node (ref "C112") (pin "2") (pinfunction "2_2") (pintype "passive"))
      (node (ref "D120") (pin "1") (pinfunction "C_1") (pintype "passive"))
      (node (ref "F106") (pin "3") (pinfunction "2_3") (pintype "passive"))
      (node (ref "F106") (pin "4") (pinfunction "2_4") (pintype "passive"))
      (node (ref "P106") (pin "1") (pinfunction "1_1") (pintype "passive"))
      (node (ref "R144") (pin "2") (pinfunction "2_2") (pintype "passive"))
      (node (ref "TP106") (pin "1") (pinfunction "1_1") (pintype "passive"))
    )
    (net (code "58") (name "Net-(D121-C)") (class "Default")
      (node (ref "C113") (pin "2") (pinfunction "2_2") (pintype "passive"))
      (node (ref "D121") (pin "1") (pinfunction "C_1") (pintype "passive"))
      (node (ref "F107") (pin "3") (pinfunction "2_3") (pintype "passive"))
      (node (ref "F107") (pin "4") (pinfunction "2_4") (pintype "passive"))
      (node (ref "P107") (pin "1") (pinfunction "1_1") (pintype "passive"))
      (node (ref "R145") (pin "2") (pinfunction "2_2") (pintype "passive"))
      (node (ref "TP107") (pin "1") (pinfunction "1_1") (pintype "passive"))
    )
    (net (code "59") (name "Net-(K100-NC)") (class "Default")
      (node (ref "K100") (pin "3") (pinfunction "NC_3") (pintype "passive"))
      (node (ref "R101") (pin "1") (pinfunction "1_1") (pintype "passive"))
    )
    (net (code "60") (name "Net-(K100-NO)") (class "Default")
      (node (ref "K100") (pin "2") (pinfunction "NO_2") (pintype "passive"))
      (node (ref "R100") (pin "1") (pinfunction "1_1") (pintype "passive"))
    )
    (net (code "61") (name "Net-(K101-NC)") (class "Default")
      (node (ref "K101") (pin "3") (pinfunction "NC_3") (pintype "passive"))
      (node (ref "R103") (pin "1") (pinfunction "1_1") (pintype "passive"))
    )
    (net (code "62") (name "Net-(K101-NO)") (class "Default")
      (node (ref "K101") (pin "2") (pinfunction "NO_2") (pintype "passive"))
      (node (ref "R102") (pin "1") (pinfunction "1_1") (pintype "passive"))
    )
    (net (code "63") (name "Net-(K102-NC)") (class "Default")
      (node (ref "K102") (pin "3") (pinfunction "NC_3") (pintype "passive"))
      (node (ref "R105") (pin "1") (pinfunction "1_1") (pintype "passive"))
    )
    (net (code "64") (name "Net-(K102-NO)") (class "Default")
      (node (ref "K102") (pin "2") (pinfunction "NO_2") (pintype "passive"))
      (node (ref "R104") (pin "1") (pinfunction "1_1") (pintype "passive"))
    )
    (net (code "65") (name "Net-(K103-NC)") (class "Default")
      (node (ref "K103") (pin "3") (pinfunction "NC_3") (pintype "passive"))
      (node (ref "R113") (pin "1") (pinfunction "1_1") (pintype "passive"))
    )
    (net (code "66") (name "Net-(K103-NO)") (class "Default")
      (node (ref "K103") (pin "2") (pinfunction "NO_2") (pintype "passive"))
      (node (ref "R112") (pin "1") (pinfunction "1_1") (pintype "passive"))
    )
    (net (code "67") (name "Net-(K104-NC)") (class "Default")
      (node (ref "K104") (pin "3") (pinfunction "NC_3") (pintype "passive"))
      (node (ref "R115") (pin "1") (pinfunction "1_1") (pintype "passive"))
    )
    (net (code "68") (name "Net-(K104-NO)") (class "Default")
      (node (ref "K104") (pin "2") (pinfunction "NO_2") (pintype "passive"))
      (node (ref "R114") (pin "1") (pinfunction "1_1") (pintype "passive"))
    )
    (net (code "69") (name "Net-(K105-NC)") (class "Default")
      (node (ref "K105") (pin "3") (pinfunction "NC_3") (pintype "passive"))
      (node (ref "R117") (pin "1") (pinfunction "1_1") (pintype "passive"))
    )
    (net (code "70") (name "Net-(K105-NO)") (class "Default")
      (node (ref "K105") (pin "2") (pinfunction "NO_2") (pintype "passive"))
      (node (ref "R116") (pin "1") (pinfunction "1_1") (pintype "passive"))
    )
    (net (code "71") (name "Net-(K106-NC)") (class "Default")
      (node (ref "K106") (pin "3") (pinfunction "NC_3") (pintype "passive"))
      (node (ref "R125") (pin "1") (pinfunction "1_1") (pintype "passive"))
    )
    (net (code "72") (name "Net-(K106-NO)") (class "Default")
      (node (ref "K106") (pin "2") (pinfunction "NO_2") (pintype "passive"))
      (node (ref "R124") (pin "1") (pinfunction "1_1") (pintype "passive"))
    )
    (net (code "73") (name "Net-(K107-NC)") (class "Default")
      (node (ref "K107") (pin "3") (pinfunction "NC_3") (pintype "passive"))
      (node (ref "R127") (pin "1") (pinfunction "1_1") (pintype "passive"))
    )
    (net (code "74") (name "Net-(K107-NO)") (class "Default")
      (node (ref "K107") (pin "2") (pinfunction "NO_2") (pintype "passive"))
      (node (ref "R126") (pin "1") (pinfunction "1_1") (pintype "passive"))
    )
    (net (code "75") (name "Net-(Q100-G)") (class "Default")
      (node (ref "Q100") (pin "1") (pinfunction "G_1") (pintype "passive"))
      (node (ref "R106") (pin "2") (pinfunction "2_2") (pintype "passive"))
      (node (ref "R108") (pin "2") (pinfunction "2_2") (pintype "passive"))
    )
    (net (code "76") (name "Net-(Q101-G)") (class "Default")
      (node (ref "Q101") (pin "1") (pinfunction "G_1") (pintype "passive"))
      (node (ref "R107") (pin "2") (pinfunction "2_2") (pintype "passive"))
      (node (ref "R110") (pin "2") (pinfunction "2_2") (pintype "passive"))
    )
    (net (code "77") (name "Net-(Q102-G)") (class "Default")
      (node (ref "Q102") (pin "1") (pinfunction "G_1") (pintype "passive"))
      (node (ref "R109") (pin "2") (pinfunction "2_2") (pintype "passive"))
      (node (ref "R111") (pin "2") (pinfunction "2_2") (pintype "passive"))
    )
    (net (code "78") (name "Net-(Q103-G)") (class "Default")
      (node (ref "Q103") (pin "1") (pinfunction "G_1") (pintype "passive"))
      (node (ref "R119") (pin "2") (pinfunction "2_2") (pintype "passive"))
      (node (ref "R121") (pin "2") (pinfunction "2_2") (pintype "passive"))
    )
    (net (code "79") (name "Net-(Q104-G)") (class "Default")
      (node (ref "Q104") (pin "1") (pinfunction "G_1") (pintype "passive"))
      (node (ref "R118") (pin "2") (pinfunction "2_2") (pintype "passive"))
      (node (ref "R120") (pin "2") (pinfunction "2_2") (pintype "passive"))
    )
    (net (code "80") (name "Net-(Q105-G)") (class "Default")
      (node (ref "Q105") (pin "1") (pinfunction "G_1") (pintype "passive"))
      (node (ref "R122") (pin "2") (pinfunction "2_2") (pintype "passive"))
      (node (ref "R123") (pin "2") (pinfunction "2_2") (pintype "passive"))
    )
    (net (code "81") (name "Net-(Q106-G)") (class "Default")
      (node (ref "Q106") (pin "1") (pinfunction "G_1") (pintype "passive"))
      (node (ref "R128") (pin "2") (pinfunction "2_2") (pintype "passive"))
      (node (ref "R129") (pin "2") (pinfunction "2_2") (pintype "passive"))
    )
    (net (code "82") (name "Net-(Q107-G)") (class "Default")
      (node (ref "Q107") (pin "1") (pinfunction "G_1") (pintype "passive"))
      (node (ref "R130") (pin "2") (pinfunction "2_2") (pintype "passive"))
      (node (ref "R131") (pin "2") (pinfunction "2_2") (pintype "passive"))
    )
    (net (code "83") (name "V+_RELAY") (class "Default")
      (node (ref "K100") (pin "5") (pinfunction "COIL2_5") (pintype "passive"))
      (node (ref "K101") (pin "5") (pinfunction "COIL2_5") (pintype "passive"))
      (node (ref "K102") (pin "5") (pinfunction "COIL2_5") (pintype "passive"))
      (node (ref "K103") (pin "5") (pinfunction "COIL2_5") (pintype "passive"))
      (node (ref "K104") (pin "5") (pinfunction "COIL2_5") (pintype "passive"))
      (node (ref "K105") (pin "5") (pinfunction "COIL2_5") (pintype "passive"))
      (node (ref "K106") (pin "5") (pinfunction "COIL2_5") (pintype "passive"))
      (node (ref "K107") (pin "5") (pinfunction "COIL2_5") (pintype "passive"))
    )
  )
)
